# EasyBMS.net
KiCad netlist of a schematic drawn in EAGLE
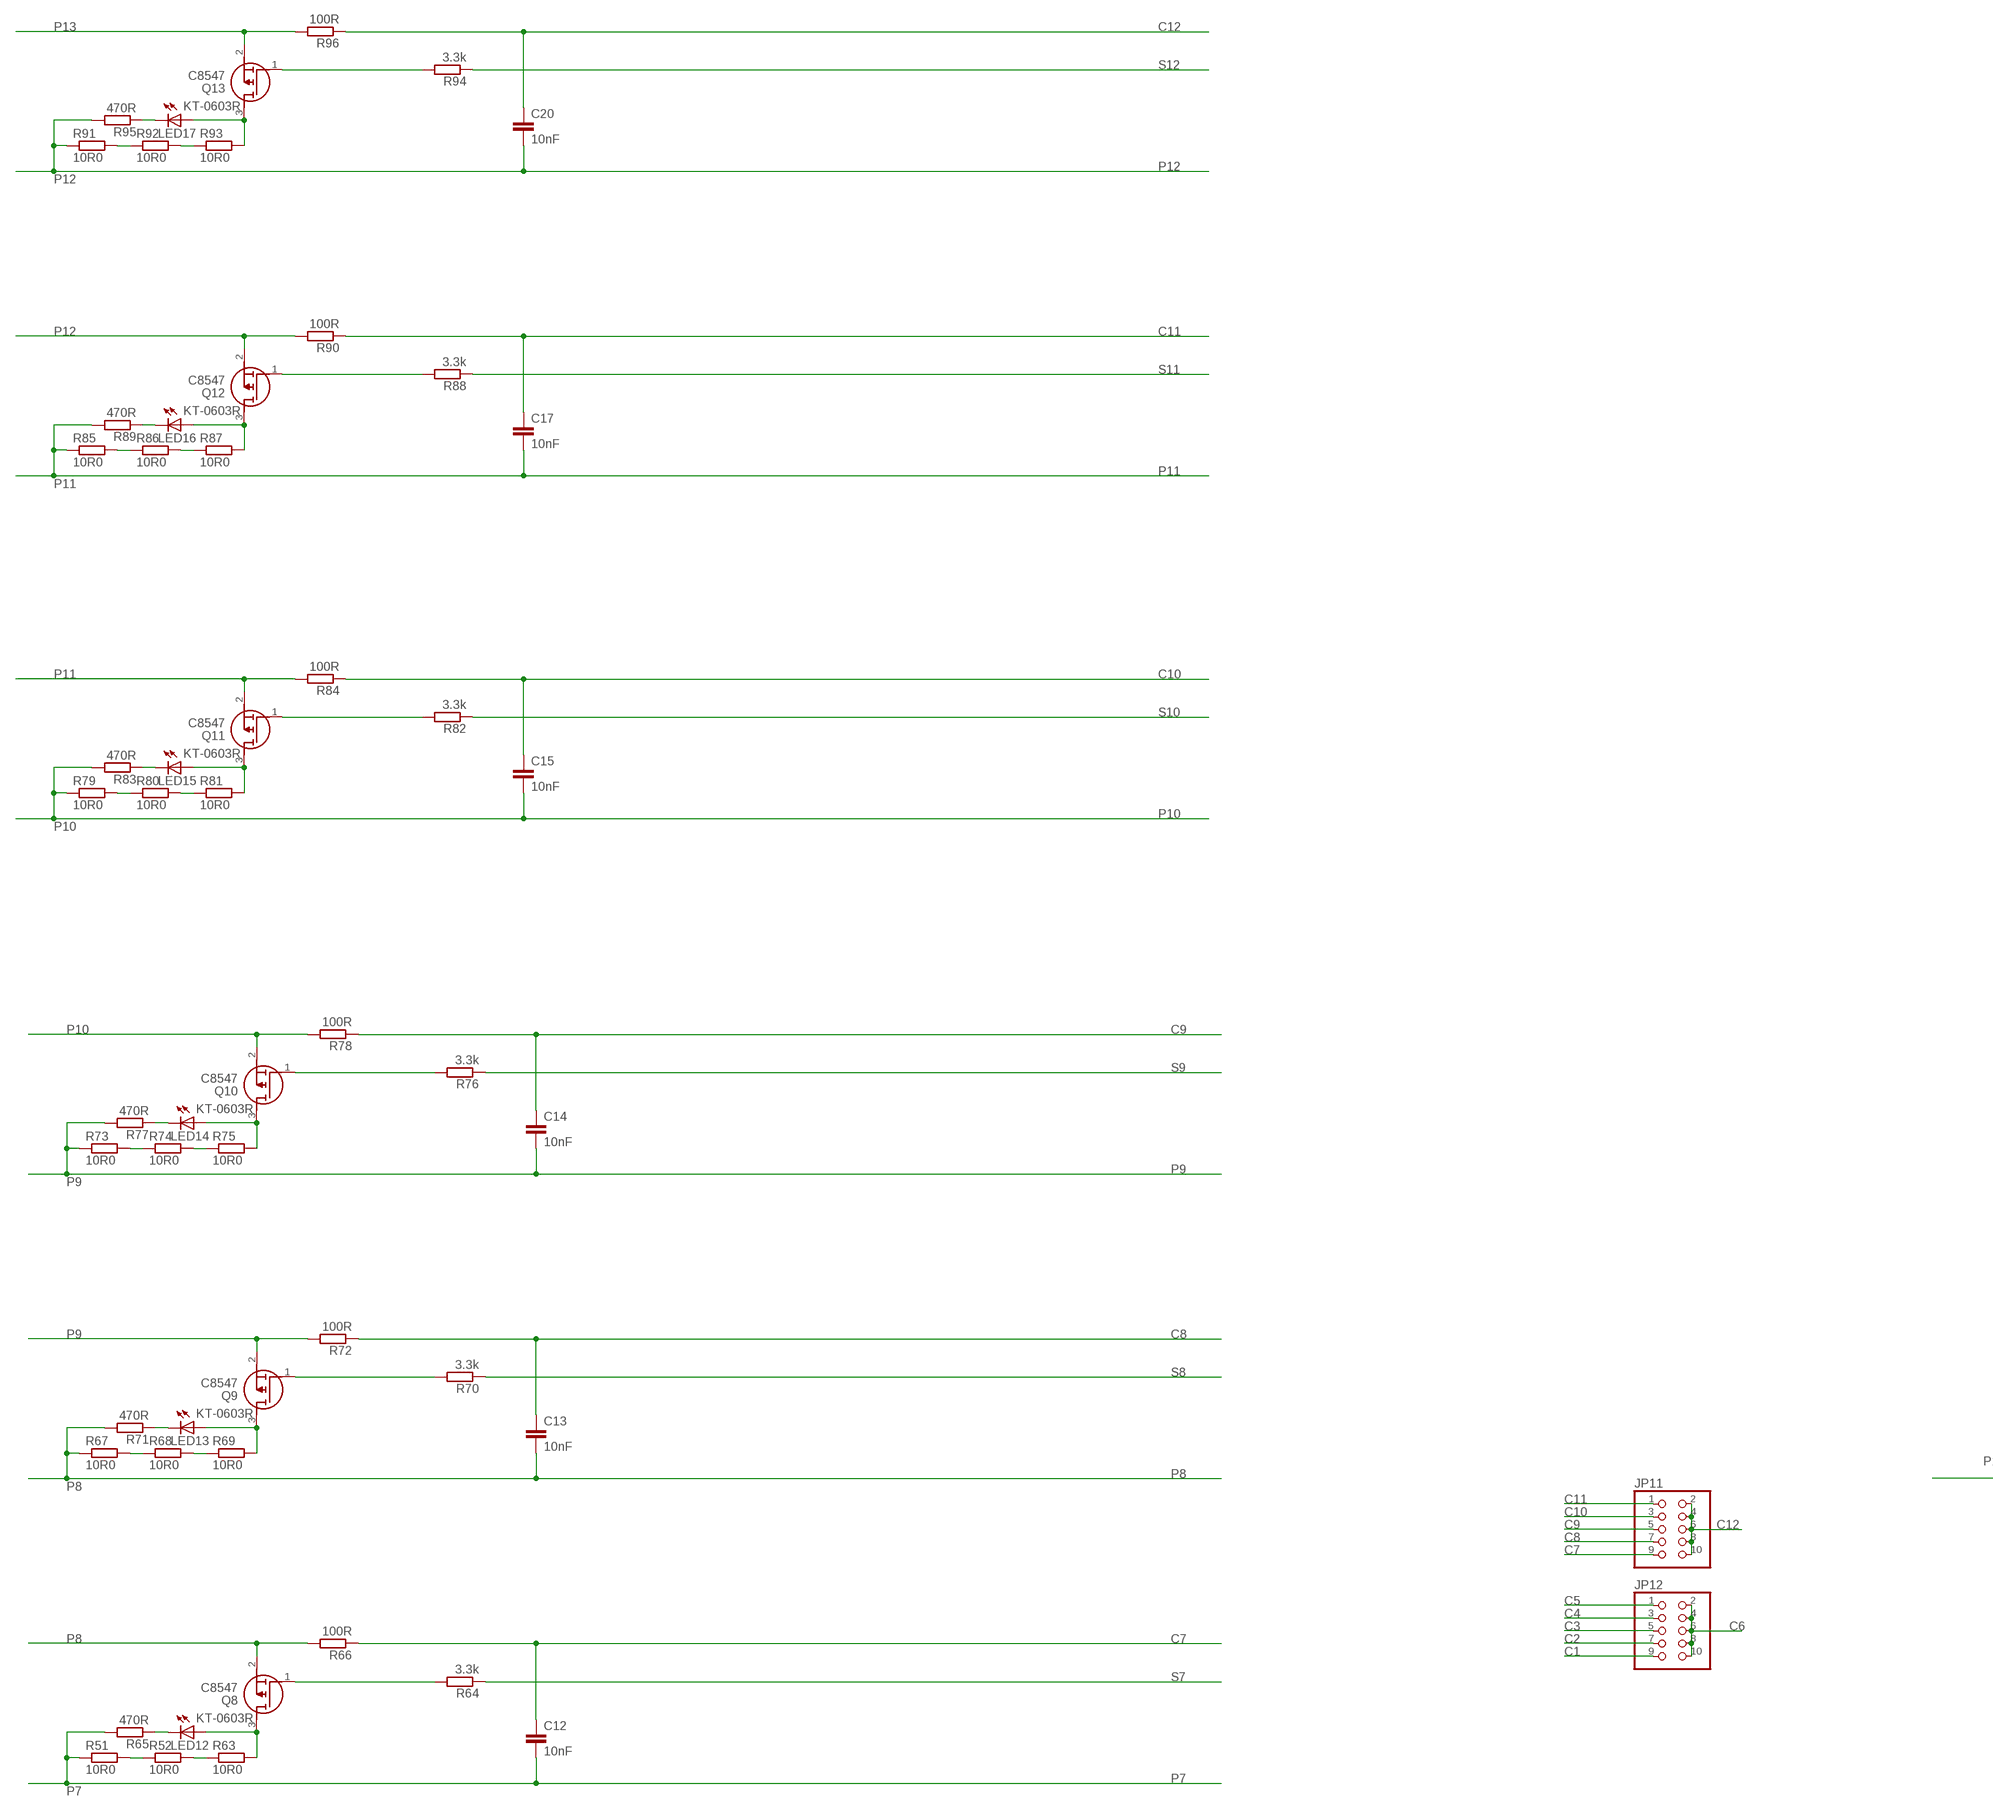
[diagram p0: schematic, sheet 1, part 1 of 3]
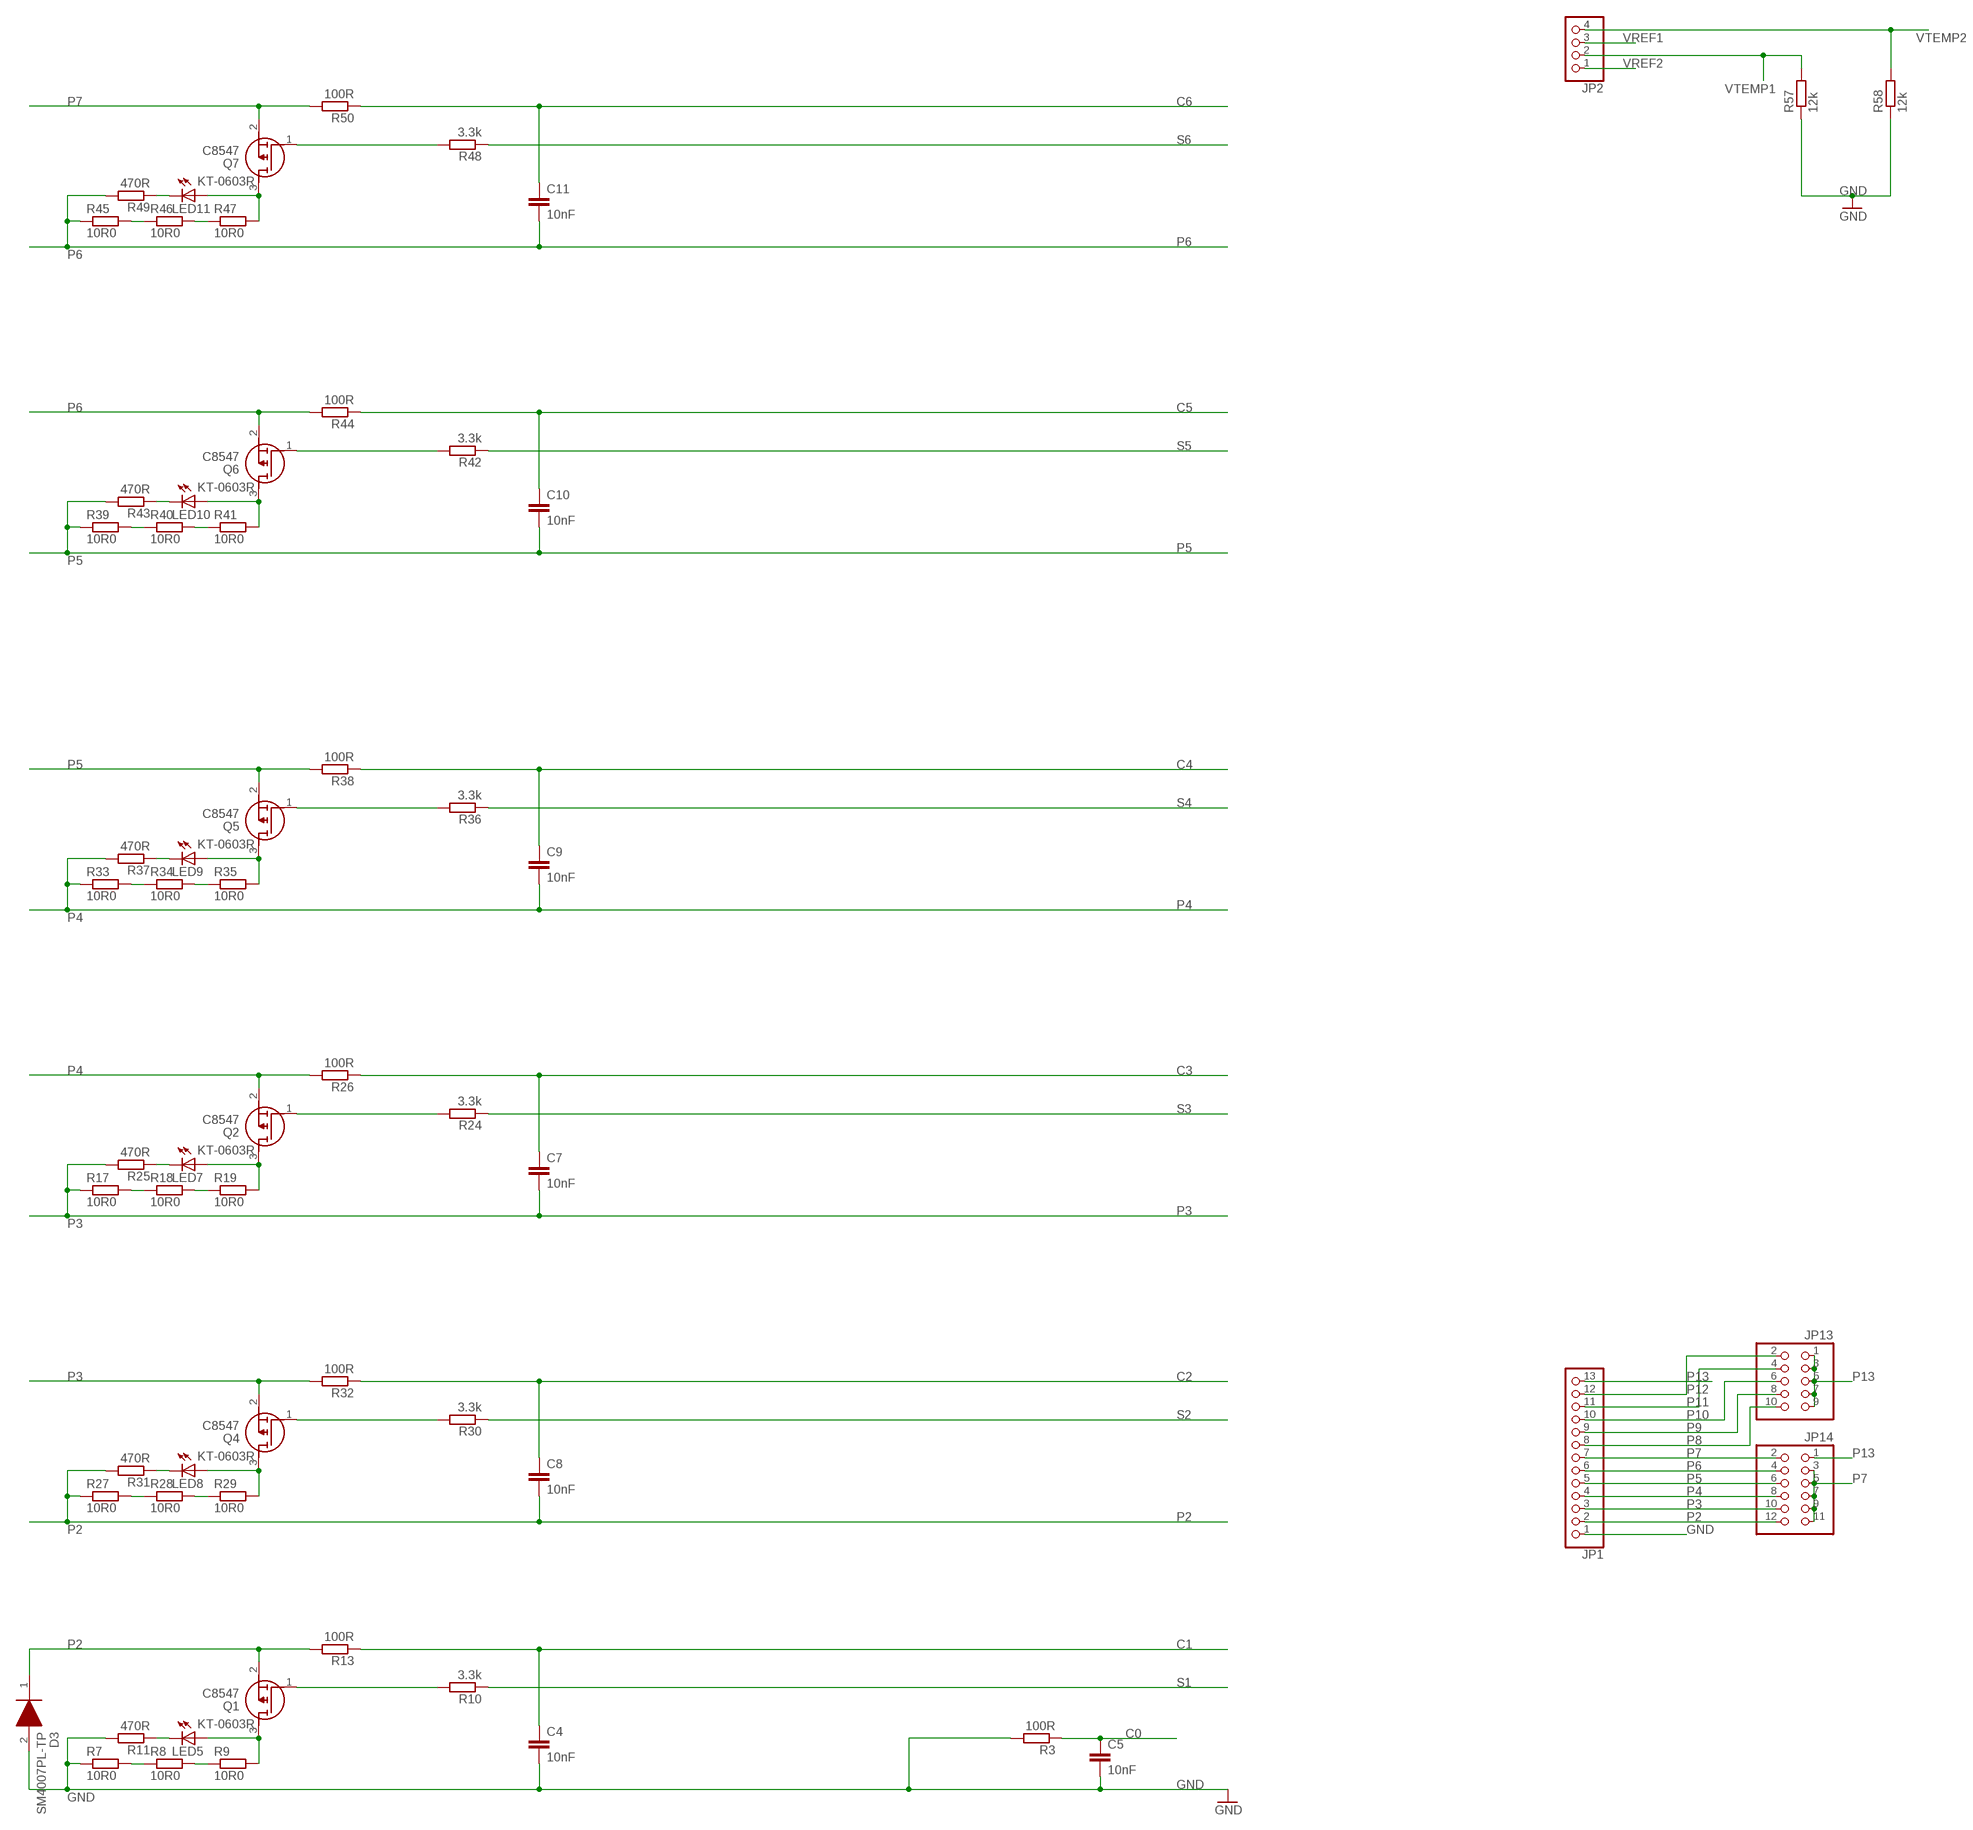
[diagram p1: schematic, sheet 1, part 2 of 3]
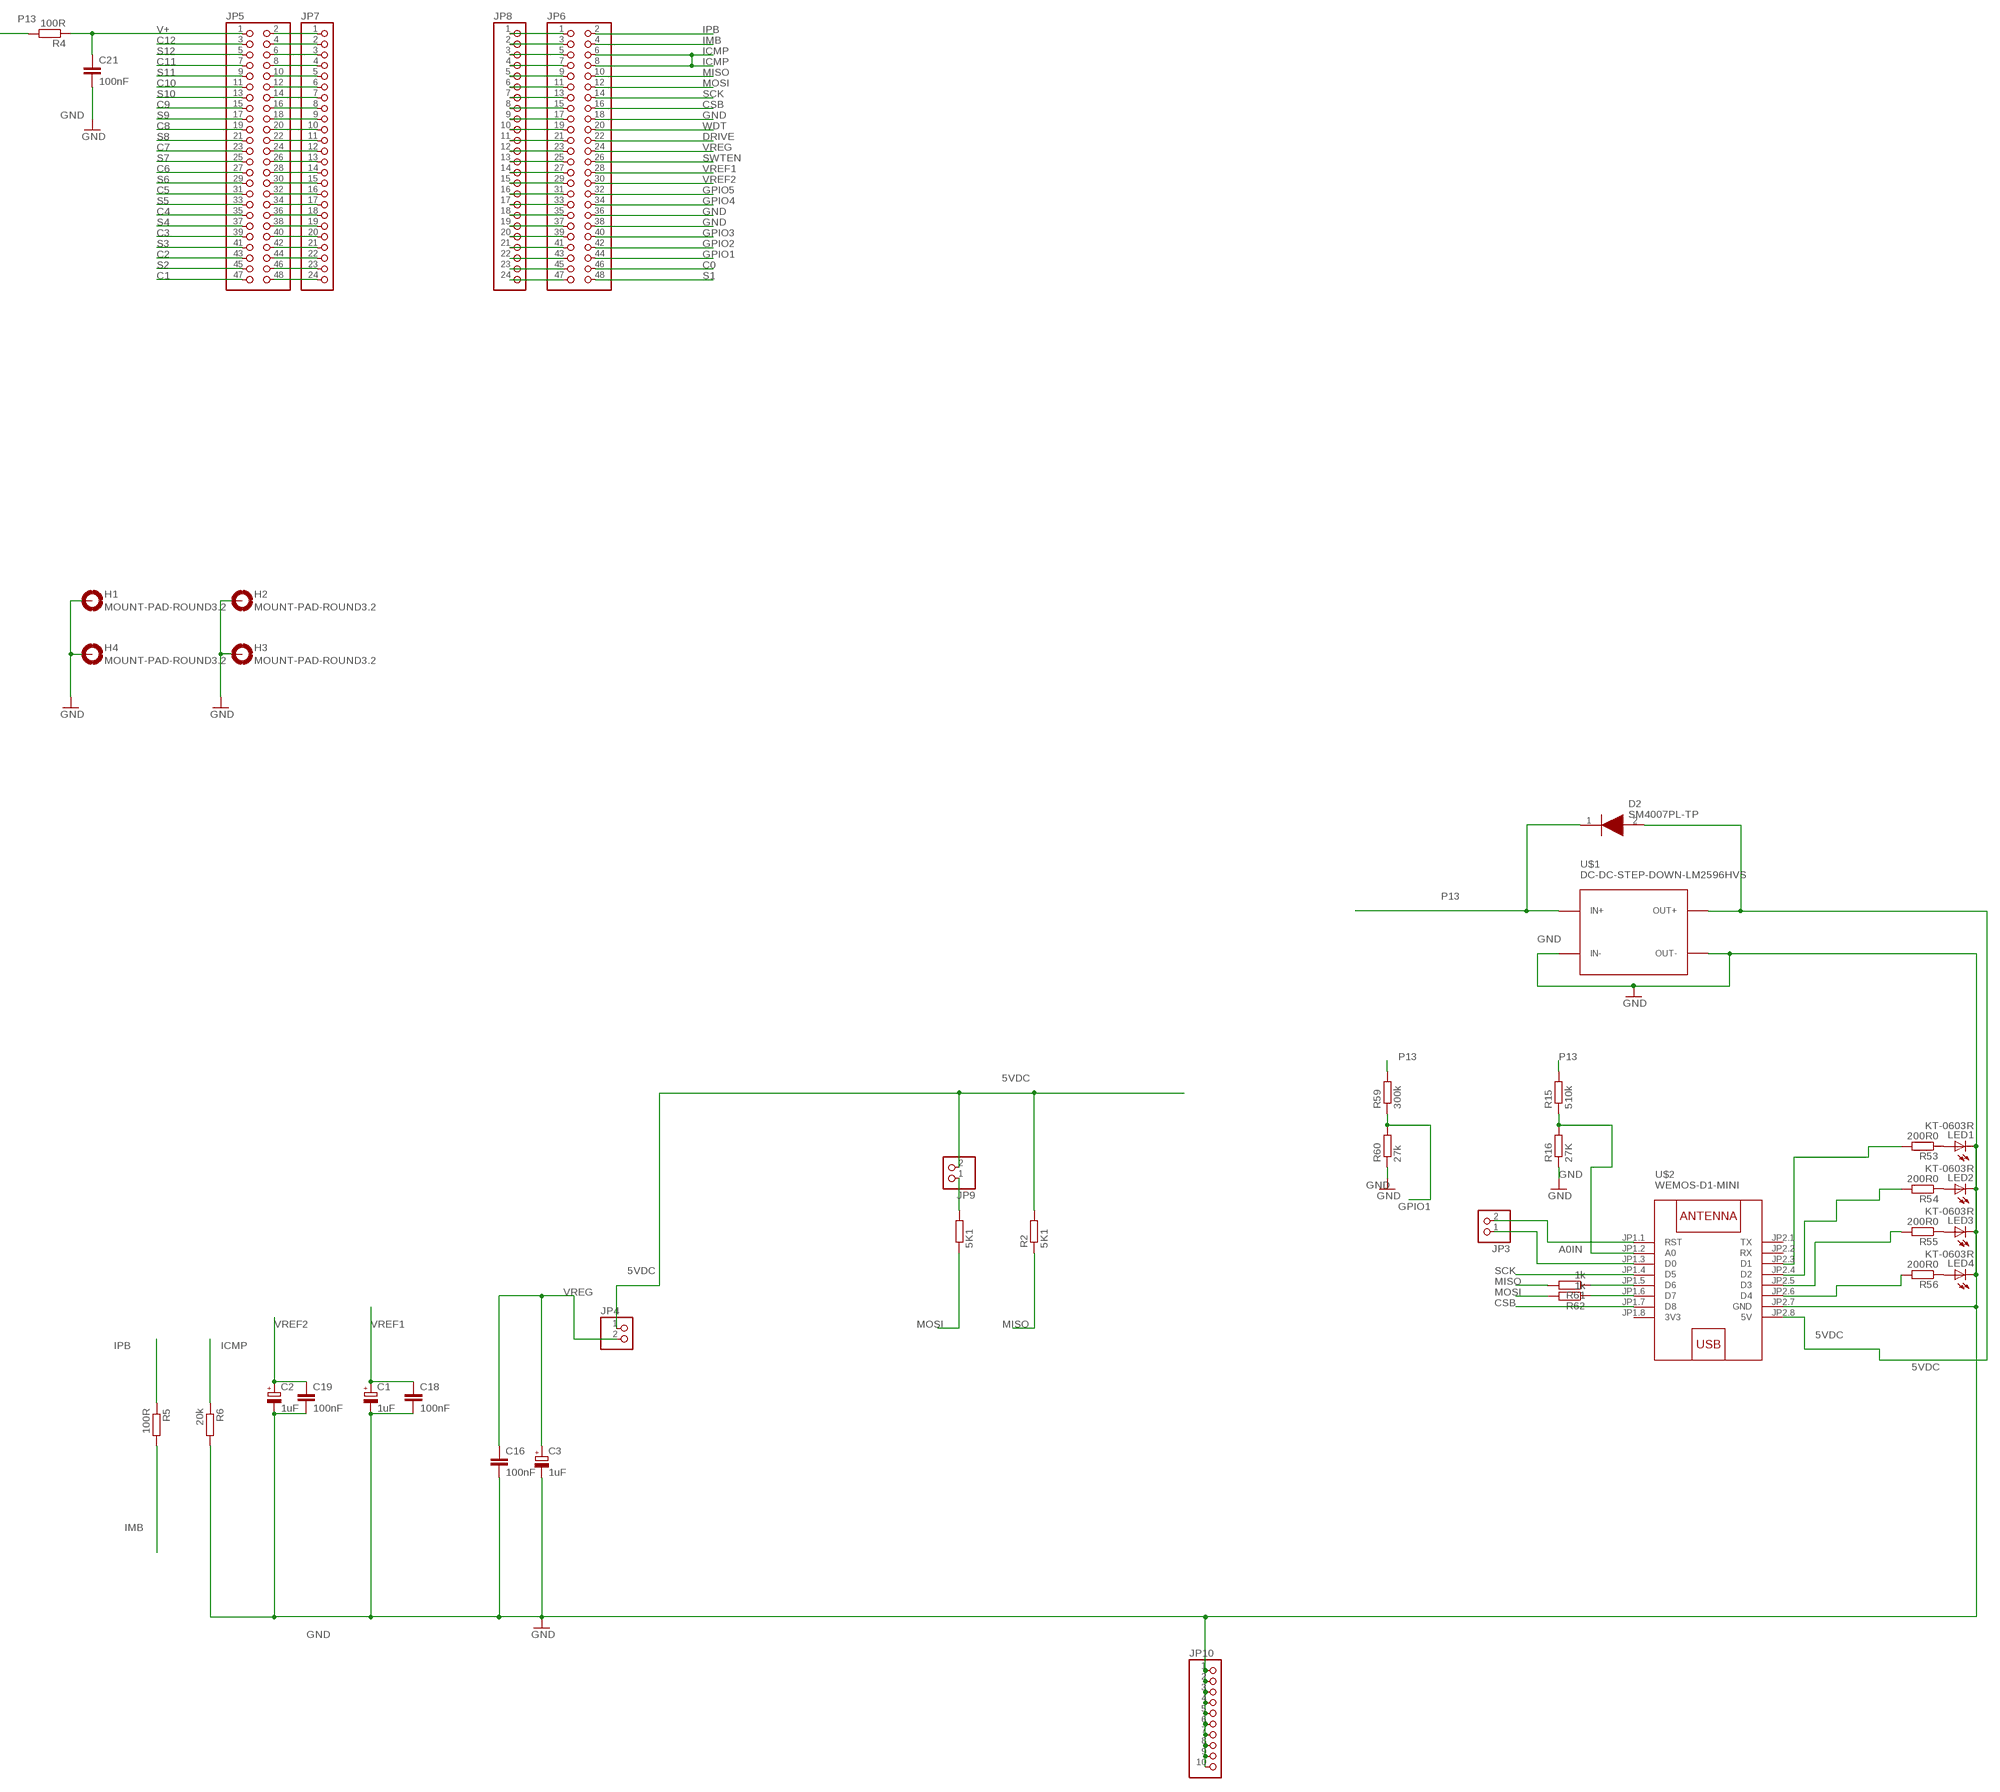
[diagram p2: schematic, sheet 1, part 3 of 3]

(export (version "E")
  (design (tool "Eeschema 10.0.6"))
  (components
    (comp (ref "C1")
      (value "1uF")
      (footprint "eagle-import:E2,5-6")
      (libsource (lib "eagle-import") (part "CPOL-EUE2.5-6"))
    )
    (comp (ref "C2")
      (value "1uF")
      (footprint "eagle-import:E2,5-6")
      (libsource (lib "eagle-import") (part "CPOL-EUE2.5-6"))
    )
    (comp (ref "C3")
      (value "1uF")
      (footprint "eagle-import:E2,5-6")
      (libsource (lib "eagle-import") (part "CPOL-EUE2.5-6"))
    )
    (comp (ref "C4")
      (value "10nF")
      (footprint "eagle-import:C0402")
      (libsource (lib "eagle-import") (part "C-EUC0402"))
    )
    (comp (ref "C5")
      (value "10nF")
      (footprint "eagle-import:C0402")
      (libsource (lib "eagle-import") (part "C-EUC0402"))
    )
    (comp (ref "C7")
      (value "10nF")
      (footprint "eagle-import:C0402")
      (libsource (lib "eagle-import") (part "C-EUC0402"))
    )
    (comp (ref "C8")
      (value "10nF")
      (footprint "eagle-import:C0402")
      (libsource (lib "eagle-import") (part "C-EUC0402"))
    )
    (comp (ref "C9")
      (value "10nF")
      (footprint "eagle-import:C0402")
      (libsource (lib "eagle-import") (part "C-EUC0402"))
    )
    (comp (ref "C10")
      (value "10nF")
      (footprint "eagle-import:C0402")
      (libsource (lib "eagle-import") (part "C-EUC0402"))
    )
    (comp (ref "C11")
      (value "10nF")
      (footprint "eagle-import:C0402")
      (libsource (lib "eagle-import") (part "C-EUC0402"))
    )
    (comp (ref "C12")
      (value "10nF")
      (footprint "eagle-import:C0402")
      (libsource (lib "eagle-import") (part "C-EUC0402"))
    )
    (comp (ref "C13")
      (value "10nF")
      (footprint "eagle-import:C0402")
      (libsource (lib "eagle-import") (part "C-EUC0402"))
    )
    (comp (ref "C14")
      (value "10nF")
      (footprint "eagle-import:C0402")
      (libsource (lib "eagle-import") (part "C-EUC0402"))
    )
    (comp (ref "C15")
      (value "10nF")
      (footprint "eagle-import:C0402")
      (libsource (lib "eagle-import") (part "C-EUC0402"))
    )
    (comp (ref "C16")
      (value "100nF")
      (footprint "eagle-import:C1206")
      (libsource (lib "eagle-import") (part "C-EUC1206"))
    )
    (comp (ref "C17")
      (value "10nF")
      (footprint "eagle-import:C0402")
      (libsource (lib "eagle-import") (part "C-EUC0402"))
    )
    (comp (ref "C18")
      (value "100nF")
      (footprint "eagle-import:C1206")
      (libsource (lib "eagle-import") (part "C-EUC1206"))
    )
    (comp (ref "C19")
      (value "100nF")
      (footprint "eagle-import:C1206")
      (libsource (lib "eagle-import") (part "C-EUC1206"))
    )
    (comp (ref "C20")
      (value "10nF")
      (footprint "eagle-import:C0402")
      (libsource (lib "eagle-import") (part "C-EUC0402"))
    )
    (comp (ref "C21")
      (value "100nF")
      (footprint "eagle-import:C1206")
      (libsource (lib "eagle-import") (part "C-EUC1206"))
    )
    (comp (ref "D2")
      (value "SM4007PL-TP")
      (footprint "eagle-import:SODFL3616X135N")
      (fields (field (name "MOUSER_PART_NUMBER") "833-SM4007PL-TP"))
      (libsource (lib "eagle-import") (part "SM4007PL-TP"))
    )
    (comp (ref "D3")
      (value "SM4007PL-TP")
      (footprint "eagle-import:SODFL3616X135N")
      (fields (field (name "MOUSER_PART_NUMBER") "833-SM4007PL-TP"))
      (libsource (lib "eagle-import") (part "SM4007PL-TP"))
    )
    (comp (ref "H1")
      (value "MOUNT-PAD-ROUND3.2")
      (footprint "eagle-import:3,2-PAD")
      (libsource (lib "eagle-import") (part "MOUNT-PAD-ROUND3.2"))
    )
    (comp (ref "H2")
      (value "MOUNT-PAD-ROUND3.2")
      (footprint "eagle-import:3,2-PAD")
      (libsource (lib "eagle-import") (part "MOUNT-PAD-ROUND3.2"))
    )
    (comp (ref "H3")
      (value "MOUNT-PAD-ROUND3.2")
      (footprint "eagle-import:3,2-PAD")
      (libsource (lib "eagle-import") (part "MOUNT-PAD-ROUND3.2"))
    )
    (comp (ref "H4")
      (value "MOUNT-PAD-ROUND3.2")
      (footprint "eagle-import:3,2-PAD")
      (libsource (lib "eagle-import") (part "MOUNT-PAD-ROUND3.2"))
    )
    (comp (ref "JP1")
      (value "PINHD-1X13/90")
      (footprint "eagle-import:1X13_90")
      (libsource (lib "eagle-import") (part "PINHD-1X13/90"))
    )
    (comp (ref "JP2")
      (value "PINHD-1X4/90")
      (footprint "eagle-import:1X04_90")
      (libsource (lib "eagle-import") (part "PINHD-1X4/90"))
    )
    (comp (ref "JP3")
      (value "PINHD-1X2")
      (footprint "eagle-import:1X02")
      (libsource (lib "eagle-import") (part "PINHD-1X2"))
    )
    (comp (ref "JP4")
      (value "PINHD-1X2")
      (footprint "eagle-import:1X02")
      (libsource (lib "eagle-import") (part "PINHD-1X2"))
    )
    (comp (ref "JP5")
      (value "PINHD-2X24")
      (footprint "eagle-import:2X24")
      (libsource (lib "eagle-import") (part "PINHD-2X24"))
    )
    (comp (ref "JP6")
      (value "PINHD-2X24")
      (footprint "eagle-import:2X24")
      (libsource (lib "eagle-import") (part "PINHD-2X24"))
    )
    (comp (ref "JP7")
      (value "PINHD-1X24")
      (footprint "eagle-import:1X24")
      (libsource (lib "eagle-import") (part "PINHD-1X24"))
    )
    (comp (ref "JP8")
      (value "PINHD-1X24")
      (footprint "eagle-import:1X24")
      (libsource (lib "eagle-import") (part "PINHD-1X24"))
    )
    (comp (ref "JP9")
      (value "PINHD-1X2")
      (footprint "eagle-import:1X02")
      (libsource (lib "eagle-import") (part "PINHD-1X2"))
    )
    (comp (ref "JP10")
      (value "PINHD-1X10")
      (footprint "eagle-import:1X10")
      (libsource (lib "eagle-import") (part "PINHD-1X10"))
    )
    (comp (ref "JP11")
      (value "PINHD-2X5")
      (footprint "eagle-import:2X05")
      (libsource (lib "eagle-import") (part "PINHD-2X5"))
    )
    (comp (ref "JP12")
      (value "PINHD-2X5")
      (footprint "eagle-import:2X05")
      (libsource (lib "eagle-import") (part "PINHD-2X5"))
    )
    (comp (ref "JP13")
      (value "PINHD-2X5")
      (footprint "eagle-import:2X05")
      (libsource (lib "eagle-import") (part "PINHD-2X5"))
    )
    (comp (ref "JP14")
      (value "PINHD-2X6")
      (footprint "eagle-import:2X06")
      (libsource (lib "eagle-import") (part "PINHD-2X6"))
    )
    (comp (ref "LED1")
      (value "KT-0603R")
      (footprint "eagle-import:CHIPLED_0603")
      (libsource (lib "eagle-import") (part "LEDCHIPLED_0603"))
    )
    (comp (ref "LED2")
      (value "KT-0603R")
      (footprint "eagle-import:CHIPLED_0603")
      (libsource (lib "eagle-import") (part "LEDCHIPLED_0603"))
    )
    (comp (ref "LED3")
      (value "KT-0603R")
      (footprint "eagle-import:CHIPLED_0603")
      (libsource (lib "eagle-import") (part "LEDCHIPLED_0603"))
    )
    (comp (ref "LED4")
      (value "KT-0603R")
      (footprint "eagle-import:CHIPLED_0603")
      (libsource (lib "eagle-import") (part "LEDCHIPLED_0603"))
    )
    (comp (ref "LED5")
      (value "KT-0603R")
      (footprint "eagle-import:CHIPLED_0603")
      (libsource (lib "eagle-import") (part "LEDCHIPLED_0603"))
    )
    (comp (ref "LED7")
      (value "KT-0603R")
      (footprint "eagle-import:CHIPLED_0603")
      (libsource (lib "eagle-import") (part "LEDCHIPLED_0603"))
    )
    (comp (ref "LED8")
      (value "KT-0603R")
      (footprint "eagle-import:CHIPLED_0603")
      (libsource (lib "eagle-import") (part "LEDCHIPLED_0603"))
    )
    (comp (ref "LED9")
      (value "KT-0603R")
      (footprint "eagle-import:CHIPLED_0603")
      (libsource (lib "eagle-import") (part "LEDCHIPLED_0603"))
    )
    (comp (ref "LED10")
      (value "KT-0603R")
      (footprint "eagle-import:CHIPLED_0603")
      (libsource (lib "eagle-import") (part "LEDCHIPLED_0603"))
    )
    (comp (ref "LED11")
      (value "KT-0603R")
      (footprint "eagle-import:CHIPLED_0603")
      (libsource (lib "eagle-import") (part "LEDCHIPLED_0603"))
    )
    (comp (ref "LED12")
      (value "KT-0603R")
      (footprint "eagle-import:CHIPLED_0603")
      (libsource (lib "eagle-import") (part "LEDCHIPLED_0603"))
    )
    (comp (ref "LED13")
      (value "KT-0603R")
      (footprint "eagle-import:CHIPLED_0603")
      (libsource (lib "eagle-import") (part "LEDCHIPLED_0603"))
    )
    (comp (ref "LED14")
      (value "KT-0603R")
      (footprint "eagle-import:CHIPLED_0603")
      (libsource (lib "eagle-import") (part "LEDCHIPLED_0603"))
    )
    (comp (ref "LED15")
      (value "KT-0603R")
      (footprint "eagle-import:CHIPLED_0603")
      (libsource (lib "eagle-import") (part "LEDCHIPLED_0603"))
    )
    (comp (ref "LED16")
      (value "KT-0603R")
      (footprint "eagle-import:CHIPLED_0603")
      (libsource (lib "eagle-import") (part "LEDCHIPLED_0603"))
    )
    (comp (ref "LED17")
      (value "KT-0603R")
      (footprint "eagle-import:CHIPLED_0603")
      (libsource (lib "eagle-import") (part "LEDCHIPLED_0603"))
    )
    (comp (ref "Q1")
      (value "C8547")
      (footprint "eagle-import:PG-SOT-23")
      (fields
        (field (name "MANUFACTURER_PART_NUMBER") "BSS308PEH6327XTSA1")
        (field (name "MOUSER_PART_NUMBER") "726-BSS308PEH6327XTS")
      )
      (libsource (lib "eagle-import") (part "BSS308PEH6327XTSA1"))
    )
    (comp (ref "Q2")
      (value "C8547")
      (footprint "eagle-import:PG-SOT-23")
      (fields
        (field (name "MANUFACTURER_PART_NUMBER") "BSS308PEH6327XTSA1")
        (field (name "MOUSER_PART_NUMBER") "726-BSS308PEH6327XTS")
      )
      (libsource (lib "eagle-import") (part "BSS308PEH6327XTSA1"))
    )
    (comp (ref "Q4")
      (value "C8547")
      (footprint "eagle-import:PG-SOT-23")
      (fields
        (field (name "MANUFACTURER_PART_NUMBER") "BSS308PEH6327XTSA1")
        (field (name "MOUSER_PART_NUMBER") "726-BSS308PEH6327XTS")
      )
      (libsource (lib "eagle-import") (part "BSS308PEH6327XTSA1"))
    )
    (comp (ref "Q5")
      (value "C8547")
      (footprint "eagle-import:PG-SOT-23")
      (fields
        (field (name "MANUFACTURER_PART_NUMBER") "BSS308PEH6327XTSA1")
        (field (name "MOUSER_PART_NUMBER") "726-BSS308PEH6327XTS")
      )
      (libsource (lib "eagle-import") (part "BSS308PEH6327XTSA1"))
    )
    (comp (ref "Q6")
      (value "C8547")
      (footprint "eagle-import:PG-SOT-23")
      (fields
        (field (name "MANUFACTURER_PART_NUMBER") "BSS308PEH6327XTSA1")
        (field (name "MOUSER_PART_NUMBER") "726-BSS308PEH6327XTS")
      )
      (libsource (lib "eagle-import") (part "BSS308PEH6327XTSA1"))
    )
    (comp (ref "Q7")
      (value "C8547")
      (footprint "eagle-import:PG-SOT-23")
      (fields
        (field (name "MANUFACTURER_PART_NUMBER") "BSS308PEH6327XTSA1")
        (field (name "MOUSER_PART_NUMBER") "726-BSS308PEH6327XTS")
      )
      (libsource (lib "eagle-import") (part "BSS308PEH6327XTSA1"))
    )
    (comp (ref "Q8")
      (value "C8547")
      (footprint "eagle-import:PG-SOT-23")
      (fields
        (field (name "MANUFACTURER_PART_NUMBER") "BSS308PEH6327XTSA1")
        (field (name "MOUSER_PART_NUMBER") "726-BSS308PEH6327XTS")
      )
      (libsource (lib "eagle-import") (part "BSS308PEH6327XTSA1"))
    )
    (comp (ref "Q9")
      (value "C8547")
      (footprint "eagle-import:PG-SOT-23")
      (fields
        (field (name "MANUFACTURER_PART_NUMBER") "BSS308PEH6327XTSA1")
        (field (name "MOUSER_PART_NUMBER") "726-BSS308PEH6327XTS")
      )
      (libsource (lib "eagle-import") (part "BSS308PEH6327XTSA1"))
    )
    (comp (ref "Q10")
      (value "C8547")
      (footprint "eagle-import:PG-SOT-23")
      (fields
        (field (name "MANUFACTURER_PART_NUMBER") "BSS308PEH6327XTSA1")
        (field (name "MOUSER_PART_NUMBER") "726-BSS308PEH6327XTS")
      )
      (libsource (lib "eagle-import") (part "BSS308PEH6327XTSA1"))
    )
    (comp (ref "Q11")
      (value "C8547")
      (footprint "eagle-import:PG-SOT-23")
      (fields
        (field (name "MANUFACTURER_PART_NUMBER") "BSS308PEH6327XTSA1")
        (field (name "MOUSER_PART_NUMBER") "726-BSS308PEH6327XTS")
      )
      (libsource (lib "eagle-import") (part "BSS308PEH6327XTSA1"))
    )
    (comp (ref "Q12")
      (value "C8547")
      (footprint "eagle-import:PG-SOT-23")
      (fields
        (field (name "MANUFACTURER_PART_NUMBER") "BSS308PEH6327XTSA1")
        (field (name "MOUSER_PART_NUMBER") "726-BSS308PEH6327XTS")
      )
      (libsource (lib "eagle-import") (part "BSS308PEH6327XTSA1"))
    )
    (comp (ref "Q13")
      (value "C8547")
      (footprint "eagle-import:PG-SOT-23")
      (fields
        (field (name "MANUFACTURER_PART_NUMBER") "BSS308PEH6327XTSA1")
        (field (name "MOUSER_PART_NUMBER") "726-BSS308PEH6327XTS")
      )
      (libsource (lib "eagle-import") (part "BSS308PEH6327XTSA1"))
    )
    (comp (ref "R1")
      (value "5K1")
      (footprint "eagle-import:R0603")
      (libsource (lib "eagle-import") (part "R-EU_R0603"))
    )
    (comp (ref "R2")
      (value "5K1")
      (footprint "eagle-import:R0603")
      (libsource (lib "eagle-import") (part "R-EU_R0603"))
    )
    (comp (ref "R3")
      (value "100R")
      (footprint "eagle-import:R0402")
      (libsource (lib "eagle-import") (part "R-EU_R0402"))
    )
    (comp (ref "R4")
      (value "100R")
      (footprint "eagle-import:R0402")
      (libsource (lib "eagle-import") (part "R-EU_R0402"))
    )
    (comp (ref "R5")
      (value "100R")
      (footprint "eagle-import:R0402")
      (libsource (lib "eagle-import") (part "R-EU_R0402"))
    )
    (comp (ref "R6")
      (value "20k")
      (footprint "eagle-import:R0603")
      (libsource (lib "eagle-import") (part "R-EU_R0603"))
    )
    (comp (ref "R7")
      (value "10R0")
      (footprint "eagle-import:R1206")
      (libsource (lib "eagle-import") (part "R-EU_R1206"))
    )
    (comp (ref "R8")
      (value "10R0")
      (footprint "eagle-import:R1206")
      (libsource (lib "eagle-import") (part "R-EU_R1206"))
    )
    (comp (ref "R9")
      (value "10R0")
      (footprint "eagle-import:R1206")
      (libsource (lib "eagle-import") (part "R-EU_R1206"))
    )
    (comp (ref "R10")
      (value "3.3k")
      (footprint "eagle-import:R0402")
      (libsource (lib "eagle-import") (part "R-EU_R0402"))
    )
    (comp (ref "R11")
      (value "470R")
      (footprint "eagle-import:R0402")
      (libsource (lib "eagle-import") (part "R-EU_R0402"))
    )
    (comp (ref "R13")
      (value "100R")
      (footprint "eagle-import:R0402")
      (libsource (lib "eagle-import") (part "R-EU_R0402"))
    )
    (comp (ref "R15")
      (value "510k")
      (footprint "eagle-import:R0603")
      (libsource (lib "eagle-import") (part "R-EU_R0603"))
    )
    (comp (ref "R16")
      (value "27K")
      (footprint "eagle-import:R0603")
      (libsource (lib "eagle-import") (part "R-EU_R0603"))
    )
    (comp (ref "R17")
      (value "10R0")
      (footprint "eagle-import:R1206")
      (libsource (lib "eagle-import") (part "R-EU_R1206"))
    )
    (comp (ref "R18")
      (value "10R0")
      (footprint "eagle-import:R1206")
      (libsource (lib "eagle-import") (part "R-EU_R1206"))
    )
    (comp (ref "R19")
      (value "10R0")
      (footprint "eagle-import:R1206")
      (libsource (lib "eagle-import") (part "R-EU_R1206"))
    )
    (comp (ref "R24")
      (value "3.3k")
      (footprint "eagle-import:R0402")
      (libsource (lib "eagle-import") (part "R-EU_R0402"))
    )
    (comp (ref "R25")
      (value "470R")
      (footprint "eagle-import:R0402")
      (libsource (lib "eagle-import") (part "R-EU_R0402"))
    )
    (comp (ref "R26")
      (value "100R")
      (footprint "eagle-import:R0402")
      (libsource (lib "eagle-import") (part "R-EU_R0402"))
    )
    (comp (ref "R27")
      (value "10R0")
      (footprint "eagle-import:R1206")
      (libsource (lib "eagle-import") (part "R-EU_R1206"))
    )
    (comp (ref "R28")
      (value "10R0")
      (footprint "eagle-import:R1206")
      (libsource (lib "eagle-import") (part "R-EU_R1206"))
    )
    (comp (ref "R29")
      (value "10R0")
      (footprint "eagle-import:R1206")
      (libsource (lib "eagle-import") (part "R-EU_R1206"))
    )
    (comp (ref "R30")
      (value "3.3k")
      (footprint "eagle-import:R0402")
      (libsource (lib "eagle-import") (part "R-EU_R0402"))
    )
    (comp (ref "R31")
      (value "470R")
      (footprint "eagle-import:R0402")
      (libsource (lib "eagle-import") (part "R-EU_R0402"))
    )
    (comp (ref "R32")
      (value "100R")
      (footprint "eagle-import:R0402")
      (libsource (lib "eagle-import") (part "R-EU_R0402"))
    )
    (comp (ref "R33")
      (value "10R0")
      (footprint "eagle-import:R1206")
      (libsource (lib "eagle-import") (part "R-EU_R1206"))
    )
    (comp (ref "R34")
      (value "10R0")
      (footprint "eagle-import:R1206")
      (libsource (lib "eagle-import") (part "R-EU_R1206"))
    )
    (comp (ref "R35")
      (value "10R0")
      (footprint "eagle-import:R1206")
      (libsource (lib "eagle-import") (part "R-EU_R1206"))
    )
    (comp (ref "R36")
      (value "3.3k")
      (footprint "eagle-import:R0402")
      (libsource (lib "eagle-import") (part "R-EU_R0402"))
    )
    (comp (ref "R37")
      (value "470R")
      (footprint "eagle-import:R0402")
      (libsource (lib "eagle-import") (part "R-EU_R0402"))
    )
    (comp (ref "R38")
      (value "100R")
      (footprint "eagle-import:R0402")
      (libsource (lib "eagle-import") (part "R-EU_R0402"))
    )
    (comp (ref "R39")
      (value "10R0")
      (footprint "eagle-import:R1206")
      (libsource (lib "eagle-import") (part "R-EU_R1206"))
    )
    (comp (ref "R40")
      (value "10R0")
      (footprint "eagle-import:R1206")
      (libsource (lib "eagle-import") (part "R-EU_R1206"))
    )
    (comp (ref "R41")
      (value "10R0")
      (footprint "eagle-import:R1206")
      (libsource (lib "eagle-import") (part "R-EU_R1206"))
    )
    (comp (ref "R42")
      (value "3.3k")
      (footprint "eagle-import:R0402")
      (libsource (lib "eagle-import") (part "R-EU_R0402"))
    )
    (comp (ref "R43")
      (value "470R")
      (footprint "eagle-import:R0402")
      (libsource (lib "eagle-import") (part "R-EU_R0402"))
    )
    (comp (ref "R44")
      (value "100R")
      (footprint "eagle-import:R0402")
      (libsource (lib "eagle-import") (part "R-EU_R0402"))
    )
    (comp (ref "R45")
      (value "10R0")
      (footprint "eagle-import:R1206")
      (libsource (lib "eagle-import") (part "R-EU_R1206"))
    )
    (comp (ref "R46")
      (value "10R0")
      (footprint "eagle-import:R1206")
      (libsource (lib "eagle-import") (part "R-EU_R1206"))
    )
    (comp (ref "R47")
      (value "10R0")
      (footprint "eagle-import:R1206")
      (libsource (lib "eagle-import") (part "R-EU_R1206"))
    )
    (comp (ref "R48")
      (value "3.3k")
      (footprint "eagle-import:R0402")
      (libsource (lib "eagle-import") (part "R-EU_R0402"))
    )
    (comp (ref "R49")
      (value "470R")
      (footprint "eagle-import:R0402")
      (libsource (lib "eagle-import") (part "R-EU_R0402"))
    )
    (comp (ref "R50")
      (value "100R")
      (footprint "eagle-import:R0402")
      (libsource (lib "eagle-import") (part "R-EU_R0402"))
    )
    (comp (ref "R51")
      (value "10R0")
      (footprint "eagle-import:R1206")
      (libsource (lib "eagle-import") (part "R-EU_R1206"))
    )
    (comp (ref "R52")
      (value "10R0")
      (footprint "eagle-import:R1206")
      (libsource (lib "eagle-import") (part "R-EU_R1206"))
    )
    (comp (ref "R53")
      (value "200R0")
      (footprint "eagle-import:R0603")
      (libsource (lib "eagle-import") (part "R-EU_R0603"))
    )
    (comp (ref "R54")
      (value "200R0")
      (footprint "eagle-import:R0603")
      (libsource (lib "eagle-import") (part "R-EU_R0603"))
    )
    (comp (ref "R55")
      (value "200R0")
      (footprint "eagle-import:R0603")
      (libsource (lib "eagle-import") (part "R-EU_R0603"))
    )
    (comp (ref "R56")
      (value "200R0")
      (footprint "eagle-import:R0603")
      (libsource (lib "eagle-import") (part "R-EU_R0603"))
    )
    (comp (ref "R57")
      (value "12k")
      (footprint "eagle-import:R0603")
      (libsource (lib "eagle-import") (part "R-EU_R0603"))
    )
    (comp (ref "R58")
      (value "12k")
      (footprint "eagle-import:R0603")
      (libsource (lib "eagle-import") (part "R-EU_R0603"))
    )
    (comp (ref "R59")
      (value "300k")
      (footprint "eagle-import:R0603")
      (libsource (lib "eagle-import") (part "R-EU_R0603"))
    )
    (comp (ref "R60")
      (value "27k")
      (footprint "eagle-import:R0603")
      (libsource (lib "eagle-import") (part "R-EU_R0603"))
    )
    (comp (ref "R61")
      (value "1k")
      (footprint "eagle-import:R0603")
      (libsource (lib "eagle-import") (part "R-EU_R0603"))
    )
    (comp (ref "R62")
      (value "1k")
      (footprint "eagle-import:R0603")
      (libsource (lib "eagle-import") (part "R-EU_R0603"))
    )
    (comp (ref "R63")
      (value "10R0")
      (footprint "eagle-import:R1206")
      (libsource (lib "eagle-import") (part "R-EU_R1206"))
    )
    (comp (ref "R64")
      (value "3.3k")
      (footprint "eagle-import:R0402")
      (libsource (lib "eagle-import") (part "R-EU_R0402"))
    )
    (comp (ref "R65")
      (value "470R")
      (footprint "eagle-import:R0402")
      (libsource (lib "eagle-import") (part "R-EU_R0402"))
    )
    (comp (ref "R66")
      (value "100R")
      (footprint "eagle-import:R0402")
      (libsource (lib "eagle-import") (part "R-EU_R0402"))
    )
    (comp (ref "R67")
      (value "10R0")
      (footprint "eagle-import:R1206")
      (libsource (lib "eagle-import") (part "R-EU_R1206"))
    )
    (comp (ref "R68")
      (value "10R0")
      (footprint "eagle-import:R1206")
      (libsource (lib "eagle-import") (part "R-EU_R1206"))
    )
    (comp (ref "R69")
      (value "10R0")
      (footprint "eagle-import:R1206")
      (libsource (lib "eagle-import") (part "R-EU_R1206"))
    )
    (comp (ref "R70")
      (value "3.3k")
      (footprint "eagle-import:R0402")
      (libsource (lib "eagle-import") (part "R-EU_R0402"))
    )
    (comp (ref "R71")
      (value "470R")
      (footprint "eagle-import:R0402")
      (libsource (lib "eagle-import") (part "R-EU_R0402"))
    )
    (comp (ref "R72")
      (value "100R")
      (footprint "eagle-import:R0402")
      (libsource (lib "eagle-import") (part "R-EU_R0402"))
    )
    (comp (ref "R73")
      (value "10R0")
      (footprint "eagle-import:R1206")
      (libsource (lib "eagle-import") (part "R-EU_R1206"))
    )
    (comp (ref "R74")
      (value "10R0")
      (footprint "eagle-import:R1206")
      (libsource (lib "eagle-import") (part "R-EU_R1206"))
    )
    (comp (ref "R75")
      (value "10R0")
      (footprint "eagle-import:R1206")
      (libsource (lib "eagle-import") (part "R-EU_R1206"))
    )
    (comp (ref "R76")
      (value "3.3k")
      (footprint "eagle-import:R0402")
      (libsource (lib "eagle-import") (part "R-EU_R0402"))
    )
    (comp (ref "R77")
      (value "470R")
      (footprint "eagle-import:R0402")
      (libsource (lib "eagle-import") (part "R-EU_R0402"))
    )
    (comp (ref "R78")
      (value "100R")
      (footprint "eagle-import:R0402")
      (libsource (lib "eagle-import") (part "R-EU_R0402"))
    )
    (comp (ref "R79")
      (value "10R0")
      (footprint "eagle-import:R1206")
      (libsource (lib "eagle-import") (part "R-EU_R1206"))
    )
    (comp (ref "R80")
      (value "10R0")
      (footprint "eagle-import:R1206")
      (libsource (lib "eagle-import") (part "R-EU_R1206"))
    )
    (comp (ref "R81")
      (value "10R0")
      (footprint "eagle-import:R1206")
      (libsource (lib "eagle-import") (part "R-EU_R1206"))
    )
    (comp (ref "R82")
      (value "3.3k")
      (footprint "eagle-import:R0402")
      (libsource (lib "eagle-import") (part "R-EU_R0402"))
    )
    (comp (ref "R83")
      (value "470R")
      (footprint "eagle-import:R0402")
      (libsource (lib "eagle-import") (part "R-EU_R0402"))
    )
    (comp (ref "R84")
      (value "100R")
      (footprint "eagle-import:R0402")
      (libsource (lib "eagle-import") (part "R-EU_R0402"))
    )
    (comp (ref "R85")
      (value "10R0")
      (footprint "eagle-import:R1206")
      (libsource (lib "eagle-import") (part "R-EU_R1206"))
    )
    (comp (ref "R86")
      (value "10R0")
      (footprint "eagle-import:R1206")
      (libsource (lib "eagle-import") (part "R-EU_R1206"))
    )
    (comp (ref "R87")
      (value "10R0")
      (footprint "eagle-import:R1206")
      (libsource (lib "eagle-import") (part "R-EU_R1206"))
    )
    (comp (ref "R88")
      (value "3.3k")
      (footprint "eagle-import:R0402")
      (libsource (lib "eagle-import") (part "R-EU_R0402"))
    )
    (comp (ref "R89")
      (value "470R")
      (footprint "eagle-import:R0402")
      (libsource (lib "eagle-import") (part "R-EU_R0402"))
    )
    (comp (ref "R90")
      (value "100R")
      (footprint "eagle-import:R0402")
      (libsource (lib "eagle-import") (part "R-EU_R0402"))
    )
    (comp (ref "R91")
      (value "10R0")
      (footprint "eagle-import:R1206")
      (libsource (lib "eagle-import") (part "R-EU_R1206"))
    )
    (comp (ref "R92")
      (value "10R0")
      (footprint "eagle-import:R1206")
      (libsource (lib "eagle-import") (part "R-EU_R1206"))
    )
    (comp (ref "R93")
      (value "10R0")
      (footprint "eagle-import:R1206")
      (libsource (lib "eagle-import") (part "R-EU_R1206"))
    )
    (comp (ref "R94")
      (value "3.3k")
      (footprint "eagle-import:R0402")
      (libsource (lib "eagle-import") (part "R-EU_R0402"))
    )
    (comp (ref "R95")
      (value "470R")
      (footprint "eagle-import:R0402")
      (libsource (lib "eagle-import") (part "R-EU_R0402"))
    )
    (comp (ref "R96")
      (value "100R")
      (footprint "eagle-import:R0402")
      (libsource (lib "eagle-import") (part "R-EU_R0402"))
    )
    (comp (ref "U$1")
      (value "DC-DC-STEP-DOWN-LM2596HVS")
      (footprint "eagle-import:DC-DC-STEP-DOWN-LM2596HVS")
      (libsource (lib "eagle-import") (part "DC-DC-STEP-DOWN-LM2596HVS"))
    )
    (comp (ref "U$2")
      (value "WEMOS-D1-MINI")
      (footprint "eagle-import:WEMOS-D1-MINI")
      (libsource (lib "eagle-import") (part "WEMOS-D1-MINI"))
    )
  )
  (nets
    (net (code "1") (name "/3V3") (class "Default")
      (node (ref "U$2") (pin "JP1.8") (pinfunction "3V3_JP1.8") (pintype "power_in"))
    )
    (net (code "2") (name "/5VDC") (class "Default")
      (node (ref "D2") (pin "2") (pinfunction "A_2") (pintype "bidirectional"))
      (node (ref "JP4") (pin "1") (pinfunction "1_1") (pintype "passive"))
      (node (ref "JP9") (pin "2") (pinfunction "2_2") (pintype "passive"))
      (node (ref "R2") (pin "2") (pinfunction "2_2") (pintype "passive"))
      (node (ref "U$1") (pin "OUT+") (pinfunction "OUT+_OUT+") (pintype "bidirectional"))
      (node (ref "U$2") (pin "JP2.8") (pinfunction "5V_JP2.8") (pintype "power_in"))
    )
    (net (code "3") (name "/A0IN") (class "Default")
      (node (ref "R15") (pin "1") (pinfunction "1_1") (pintype "passive"))
      (node (ref "R16") (pin "2") (pinfunction "2_2") (pintype "passive"))
      (node (ref "U$2") (pin "JP1.2") (pinfunction "A0_JP1.2") (pintype "bidirectional"))
    )
    (net (code "4") (name "/C0") (class "Default")
      (node (ref "C5") (pin "1") (pinfunction "1_1") (pintype "passive"))
      (node (ref "JP6") (pin "46") (pinfunction "46_46") (pintype "passive"))
      (node (ref "R3") (pin "1") (pinfunction "1_1") (pintype "passive"))
    )
    (net (code "5") (name "/C1") (class "Default")
      (node (ref "C4") (pin "1") (pinfunction "1_1") (pintype "passive"))
      (node (ref "JP12") (pin "9") (pinfunction "9_9") (pintype "passive"))
      (node (ref "JP5") (pin "47") (pinfunction "47_47") (pintype "passive"))
      (node (ref "R13") (pin "1") (pinfunction "1_1") (pintype "passive"))
    )
    (net (code "6") (name "/C2") (class "Default")
      (node (ref "C8") (pin "1") (pinfunction "1_1") (pintype "passive"))
      (node (ref "JP12") (pin "7") (pinfunction "7_7") (pintype "passive"))
      (node (ref "JP5") (pin "43") (pinfunction "43_43") (pintype "passive"))
      (node (ref "R32") (pin "1") (pinfunction "1_1") (pintype "passive"))
    )
    (net (code "7") (name "/C3") (class "Default")
      (node (ref "C7") (pin "1") (pinfunction "1_1") (pintype "passive"))
      (node (ref "JP12") (pin "5") (pinfunction "5_5") (pintype "passive"))
      (node (ref "JP5") (pin "39") (pinfunction "39_39") (pintype "passive"))
      (node (ref "R26") (pin "1") (pinfunction "1_1") (pintype "passive"))
    )
    (net (code "8") (name "/C4") (class "Default")
      (node (ref "C9") (pin "1") (pinfunction "1_1") (pintype "passive"))
      (node (ref "JP12") (pin "3") (pinfunction "3_3") (pintype "passive"))
      (node (ref "JP5") (pin "35") (pinfunction "35_35") (pintype "passive"))
      (node (ref "R38") (pin "1") (pinfunction "1_1") (pintype "passive"))
    )
    (net (code "9") (name "/C5") (class "Default")
      (node (ref "C10") (pin "1") (pinfunction "1_1") (pintype "passive"))
      (node (ref "JP12") (pin "1") (pinfunction "1_1") (pintype "passive"))
      (node (ref "JP5") (pin "31") (pinfunction "31_31") (pintype "passive"))
      (node (ref "R44") (pin "1") (pinfunction "1_1") (pintype "passive"))
    )
    (net (code "10") (name "/C6") (class "Default")
      (node (ref "C11") (pin "1") (pinfunction "1_1") (pintype "passive"))
      (node (ref "JP12") (pin "10") (pinfunction "10_10") (pintype "passive"))
      (node (ref "JP12") (pin "2") (pinfunction "2_2") (pintype "passive"))
      (node (ref "JP12") (pin "4") (pinfunction "4_4") (pintype "passive"))
      (node (ref "JP12") (pin "6") (pinfunction "6_6") (pintype "passive"))
      (node (ref "JP12") (pin "8") (pinfunction "8_8") (pintype "passive"))
      (node (ref "JP5") (pin "27") (pinfunction "27_27") (pintype "passive"))
      (node (ref "R50") (pin "1") (pinfunction "1_1") (pintype "passive"))
    )
    (net (code "11") (name "/C7") (class "Default")
      (node (ref "C12") (pin "1") (pinfunction "1_1") (pintype "passive"))
      (node (ref "JP11") (pin "9") (pinfunction "9_9") (pintype "passive"))
      (node (ref "JP5") (pin "23") (pinfunction "23_23") (pintype "passive"))
      (node (ref "R66") (pin "1") (pinfunction "1_1") (pintype "passive"))
    )
    (net (code "12") (name "/C8") (class "Default")
      (node (ref "C13") (pin "1") (pinfunction "1_1") (pintype "passive"))
      (node (ref "JP11") (pin "7") (pinfunction "7_7") (pintype "passive"))
      (node (ref "JP5") (pin "19") (pinfunction "19_19") (pintype "passive"))
      (node (ref "R72") (pin "1") (pinfunction "1_1") (pintype "passive"))
    )
    (net (code "13") (name "/C9") (class "Default")
      (node (ref "C14") (pin "1") (pinfunction "1_1") (pintype "passive"))
      (node (ref "JP11") (pin "5") (pinfunction "5_5") (pintype "passive"))
      (node (ref "JP5") (pin "15") (pinfunction "15_15") (pintype "passive"))
      (node (ref "R78") (pin "1") (pinfunction "1_1") (pintype "passive"))
    )
    (net (code "14") (name "/C10") (class "Default")
      (node (ref "C15") (pin "1") (pinfunction "1_1") (pintype "passive"))
      (node (ref "JP11") (pin "3") (pinfunction "3_3") (pintype "passive"))
      (node (ref "JP5") (pin "11") (pinfunction "11_11") (pintype "passive"))
      (node (ref "R84") (pin "1") (pinfunction "1_1") (pintype "passive"))
    )
    (net (code "15") (name "/C11") (class "Default")
      (node (ref "C17") (pin "1") (pinfunction "1_1") (pintype "passive"))
      (node (ref "JP11") (pin "1") (pinfunction "1_1") (pintype "passive"))
      (node (ref "JP5") (pin "7") (pinfunction "7_7") (pintype "passive"))
      (node (ref "R90") (pin "1") (pinfunction "1_1") (pintype "passive"))
    )
    (net (code "16") (name "/C12") (class "Default")
      (node (ref "C20") (pin "1") (pinfunction "1_1") (pintype "passive"))
      (node (ref "JP11") (pin "10") (pinfunction "10_10") (pintype "passive"))
      (node (ref "JP11") (pin "2") (pinfunction "2_2") (pintype "passive"))
      (node (ref "JP11") (pin "4") (pinfunction "4_4") (pintype "passive"))
      (node (ref "JP11") (pin "6") (pinfunction "6_6") (pintype "passive"))
      (node (ref "JP11") (pin "8") (pinfunction "8_8") (pintype "passive"))
      (node (ref "JP5") (pin "3") (pinfunction "3_3") (pintype "passive"))
      (node (ref "R96") (pin "1") (pinfunction "1_1") (pintype "passive"))
    )
    (net (code "17") (name "/CSB") (class "Default")
      (node (ref "JP6") (pin "16") (pinfunction "16_16") (pintype "passive"))
      (node (ref "U$2") (pin "JP1.7") (pinfunction "D8_JP1.7") (pintype "bidirectional"))
    )
    (net (code "18") (name "/DRIVE") (class "Default")
      (node (ref "JP6") (pin "22") (pinfunction "22_22") (pintype "passive"))
    )
    (net (code "19") (name "/GPIO1") (class "Default")
      (node (ref "JP6") (pin "44") (pinfunction "44_44") (pintype "passive"))
      (node (ref "R59") (pin "1") (pinfunction "1_1") (pintype "passive"))
      (node (ref "R60") (pin "2") (pinfunction "2_2") (pintype "passive"))
    )
    (net (code "20") (name "/GPIO2") (class "Default")
      (node (ref "JP6") (pin "42") (pinfunction "42_42") (pintype "passive"))
    )
    (net (code "21") (name "/GPIO3") (class "Default")
      (node (ref "JP6") (pin "40") (pinfunction "40_40") (pintype "passive"))
    )
    (net (code "22") (name "/GPIO4") (class "Default")
      (node (ref "JP6") (pin "34") (pinfunction "34_34") (pintype "passive"))
    )
    (net (code "23") (name "/GPIO5") (class "Default")
      (node (ref "JP6") (pin "32") (pinfunction "32_32") (pintype "passive"))
    )
    (net (code "24") (name "/ICMP") (class "Default")
      (node (ref "JP6") (pin "6") (pinfunction "6_6") (pintype "passive"))
      (node (ref "JP6") (pin "8") (pinfunction "8_8") (pintype "passive"))
      (node (ref "R6") (pin "1") (pinfunction "1_1") (pintype "passive"))
    )
    (net (code "25") (name "/IMB") (class "Default")
      (node (ref "JP6") (pin "4") (pinfunction "4_4") (pintype "passive"))
      (node (ref "R5") (pin "2") (pinfunction "2_2") (pintype "passive"))
    )
    (net (code "26") (name "/IPB") (class "Default")
      (node (ref "JP6") (pin "2") (pinfunction "2_2") (pintype "passive"))
      (node (ref "R5") (pin "1") (pinfunction "1_1") (pintype "passive"))
    )
    (net (code "27") (name "/MISO") (class "Default")
      (node (ref "JP6") (pin "10") (pinfunction "10_10") (pintype "passive"))
      (node (ref "R2") (pin "1") (pinfunction "1_1") (pintype "passive"))
      (node (ref "R61") (pin "2") (pinfunction "2_2") (pintype "passive"))
    )
    (net (code "28") (name "/MOSI") (class "Default")
      (node (ref "JP6") (pin "12") (pinfunction "12_12") (pintype "passive"))
      (node (ref "R1") (pin "1") (pinfunction "1_1") (pintype "passive"))
      (node (ref "R62") (pin "2") (pinfunction "2_2") (pintype "passive"))
    )
    (net (code "29") (name "/P2") (class "Default")
      (node (ref "C8") (pin "2") (pinfunction "2_2") (pintype "passive"))
      (node (ref "D3") (pin "1") (pinfunction "K_1") (pintype "bidirectional"))
      (node (ref "JP1") (pin "2") (pinfunction "2_2") (pintype "passive"))
      (node (ref "JP14") (pin "12") (pinfunction "12_12") (pintype "passive"))
      (node (ref "Q1") (pin "2") (pinfunction "S_2") (pintype "bidirectional"))
      (node (ref "R13") (pin "2") (pinfunction "2_2") (pintype "passive"))
      (node (ref "R27") (pin "1") (pinfunction "1_1") (pintype "passive"))
      (node (ref "R31") (pin "2") (pinfunction "2_2") (pintype "passive"))
    )
    (net (code "30") (name "/P3") (class "Default")
      (node (ref "C7") (pin "2") (pinfunction "2_2") (pintype "passive"))
      (node (ref "JP1") (pin "3") (pinfunction "3_3") (pintype "passive"))
      (node (ref "JP14") (pin "10") (pinfunction "10_10") (pintype "passive"))
      (node (ref "Q4") (pin "2") (pinfunction "S_2") (pintype "bidirectional"))
      (node (ref "R17") (pin "1") (pinfunction "1_1") (pintype "passive"))
      (node (ref "R25") (pin "2") (pinfunction "2_2") (pintype "passive"))
      (node (ref "R32") (pin "2") (pinfunction "2_2") (pintype "passive"))
    )
    (net (code "31") (name "/P4") (class "Default")
      (node (ref "C9") (pin "2") (pinfunction "2_2") (pintype "passive"))
      (node (ref "JP1") (pin "4") (pinfunction "4_4") (pintype "passive"))
      (node (ref "JP14") (pin "8") (pinfunction "8_8") (pintype "passive"))
      (node (ref "Q2") (pin "2") (pinfunction "S_2") (pintype "bidirectional"))
      (node (ref "R26") (pin "2") (pinfunction "2_2") (pintype "passive"))
      (node (ref "R33") (pin "1") (pinfunction "1_1") (pintype "passive"))
      (node (ref "R37") (pin "2") (pinfunction "2_2") (pintype "passive"))
    )
    (net (code "32") (name "/P5") (class "Default")
      (node (ref "C10") (pin "2") (pinfunction "2_2") (pintype "passive"))
      (node (ref "JP1") (pin "5") (pinfunction "5_5") (pintype "passive"))
      (node (ref "JP14") (pin "6") (pinfunction "6_6") (pintype "passive"))
      (node (ref "Q5") (pin "2") (pinfunction "S_2") (pintype "bidirectional"))
      (node (ref "R38") (pin "2") (pinfunction "2_2") (pintype "passive"))
      (node (ref "R39") (pin "1") (pinfunction "1_1") (pintype "passive"))
      (node (ref "R43") (pin "2") (pinfunction "2_2") (pintype "passive"))
    )
    (net (code "33") (name "/P6") (class "Default")
      (node (ref "C11") (pin "2") (pinfunction "2_2") (pintype "passive"))
      (node (ref "JP1") (pin "6") (pinfunction "6_6") (pintype "passive"))
      (node (ref "JP14") (pin "4") (pinfunction "4_4") (pintype "passive"))
      (node (ref "Q6") (pin "2") (pinfunction "S_2") (pintype "bidirectional"))
      (node (ref "R44") (pin "2") (pinfunction "2_2") (pintype "passive"))
      (node (ref "R45") (pin "1") (pinfunction "1_1") (pintype "passive"))
      (node (ref "R49") (pin "2") (pinfunction "2_2") (pintype "passive"))
    )
    (net (code "34") (name "/P7") (class "Default")
      (node (ref "C12") (pin "2") (pinfunction "2_2") (pintype "passive"))
      (node (ref "JP1") (pin "7") (pinfunction "7_7") (pintype "passive"))
      (node (ref "JP14") (pin "11") (pinfunction "11_11") (pintype "passive"))
      (node (ref "JP14") (pin "2") (pinfunction "2_2") (pintype "passive"))
      (node (ref "JP14") (pin "3") (pinfunction "3_3") (pintype "passive"))
      (node (ref "JP14") (pin "5") (pinfunction "5_5") (pintype "passive"))
      (node (ref "JP14") (pin "7") (pinfunction "7_7") (pintype "passive"))
      (node (ref "JP14") (pin "9") (pinfunction "9_9") (pintype "passive"))
      (node (ref "Q7") (pin "2") (pinfunction "S_2") (pintype "bidirectional"))
      (node (ref "R50") (pin "2") (pinfunction "2_2") (pintype "passive"))
      (node (ref "R51") (pin "1") (pinfunction "1_1") (pintype "passive"))
      (node (ref "R65") (pin "2") (pinfunction "2_2") (pintype "passive"))
    )
    (net (code "35") (name "/P8") (class "Default")
      (node (ref "C13") (pin "2") (pinfunction "2_2") (pintype "passive"))
      (node (ref "JP1") (pin "8") (pinfunction "8_8") (pintype "passive"))
      (node (ref "JP13") (pin "10") (pinfunction "10_10") (pintype "passive"))
      (node (ref "Q8") (pin "2") (pinfunction "S_2") (pintype "bidirectional"))
      (node (ref "R66") (pin "2") (pinfunction "2_2") (pintype "passive"))
      (node (ref "R67") (pin "1") (pinfunction "1_1") (pintype "passive"))
      (node (ref "R71") (pin "2") (pinfunction "2_2") (pintype "passive"))
    )
    (net (code "36") (name "/P9") (class "Default")
      (node (ref "C14") (pin "2") (pinfunction "2_2") (pintype "passive"))
      (node (ref "JP1") (pin "9") (pinfunction "9_9") (pintype "passive"))
      (node (ref "JP13") (pin "8") (pinfunction "8_8") (pintype "passive"))
      (node (ref "Q9") (pin "2") (pinfunction "S_2") (pintype "bidirectional"))
      (node (ref "R72") (pin "2") (pinfunction "2_2") (pintype "passive"))
      (node (ref "R73") (pin "1") (pinfunction "1_1") (pintype "passive"))
      (node (ref "R77") (pin "2") (pinfunction "2_2") (pintype "passive"))
    )
    (net (code "37") (name "/P10") (class "Default")
      (node (ref "C15") (pin "2") (pinfunction "2_2") (pintype "passive"))
      (node (ref "JP1") (pin "10") (pinfunction "10_10") (pintype "passive"))
      (node (ref "JP13") (pin "6") (pinfunction "6_6") (pintype "passive"))
      (node (ref "Q10") (pin "2") (pinfunction "S_2") (pintype "bidirectional"))
      (node (ref "R78") (pin "2") (pinfunction "2_2") (pintype "passive"))
      (node (ref "R79") (pin "1") (pinfunction "1_1") (pintype "passive"))
      (node (ref "R83") (pin "2") (pinfunction "2_2") (pintype "passive"))
    )
    (net (code "38") (name "/P11") (class "Default")
      (node (ref "C17") (pin "2") (pinfunction "2_2") (pintype "passive"))
      (node (ref "JP1") (pin "11") (pinfunction "11_11") (pintype "passive"))
      (node (ref "JP13") (pin "4") (pinfunction "4_4") (pintype "passive"))
      (node (ref "Q11") (pin "2") (pinfunction "S_2") (pintype "bidirectional"))
      (node (ref "R84") (pin "2") (pinfunction "2_2") (pintype "passive"))
      (node (ref "R85") (pin "1") (pinfunction "1_1") (pintype "passive"))
      (node (ref "R89") (pin "2") (pinfunction "2_2") (pintype "passive"))
    )
    (net (code "39") (name "/P12") (class "Default")
      (node (ref "C20") (pin "2") (pinfunction "2_2") (pintype "passive"))
      (node (ref "JP1") (pin "12") (pinfunction "12_12") (pintype "passive"))
      (node (ref "JP13") (pin "2") (pinfunction "2_2") (pintype "passive"))
      (node (ref "Q12") (pin "2") (pinfunction "S_2") (pintype "bidirectional"))
      (node (ref "R90") (pin "2") (pinfunction "2_2") (pintype "passive"))
      (node (ref "R91") (pin "1") (pinfunction "1_1") (pintype "passive"))
      (node (ref "R95") (pin "2") (pinfunction "2_2") (pintype "passive"))
    )
    (net (code "40") (name "/P13") (class "Default")
      (node (ref "D2") (pin "1") (pinfunction "K_1") (pintype "bidirectional"))
      (node (ref "JP1") (pin "13") (pinfunction "13_13") (pintype "passive"))
      (node (ref "JP13") (pin "1") (pinfunction "1_1") (pintype "passive"))
      (node (ref "JP13") (pin "3") (pinfunction "3_3") (pintype "passive"))
      (node (ref "JP13") (pin "5") (pinfunction "5_5") (pintype "passive"))
      (node (ref "JP13") (pin "7") (pinfunction "7_7") (pintype "passive"))
      (node (ref "JP13") (pin "9") (pinfunction "9_9") (pintype "passive"))
      (node (ref "JP14") (pin "1") (pinfunction "1_1") (pintype "passive"))
      (node (ref "Q13") (pin "2") (pinfunction "S_2") (pintype "bidirectional"))
      (node (ref "R15") (pin "2") (pinfunction "2_2") (pintype "passive"))
      (node (ref "R4") (pin "2") (pinfunction "2_2") (pintype "passive"))
      (node (ref "R59") (pin "2") (pinfunction "2_2") (pintype "passive"))
      (node (ref "R96") (pin "2") (pinfunction "2_2") (pintype "passive"))
      (node (ref "U$1") (pin "IN+") (pinfunction "IN+_IN+") (pintype "bidirectional"))
    )
    (net (code "41") (name "/S1") (class "Default")
      (node (ref "JP6") (pin "48") (pinfunction "48_48") (pintype "passive"))
      (node (ref "R10") (pin "1") (pinfunction "1_1") (pintype "passive"))
    )
    (net (code "42") (name "/S2") (class "Default")
      (node (ref "JP5") (pin "45") (pinfunction "45_45") (pintype "passive"))
      (node (ref "R30") (pin "1") (pinfunction "1_1") (pintype "passive"))
    )
    (net (code "43") (name "/S3") (class "Default")
      (node (ref "JP5") (pin "41") (pinfunction "41_41") (pintype "passive"))
      (node (ref "R24") (pin "1") (pinfunction "1_1") (pintype "passive"))
    )
    (net (code "44") (name "/S4") (class "Default")
      (node (ref "JP5") (pin "37") (pinfunction "37_37") (pintype "passive"))
      (node (ref "R36") (pin "1") (pinfunction "1_1") (pintype "passive"))
    )
    (net (code "45") (name "/S5") (class "Default")
      (node (ref "JP5") (pin "33") (pinfunction "33_33") (pintype "passive"))
      (node (ref "R42") (pin "1") (pinfunction "1_1") (pintype "passive"))
    )
    (net (code "46") (name "/S6") (class "Default")
      (node (ref "JP5") (pin "29") (pinfunction "29_29") (pintype "passive"))
      (node (ref "R48") (pin "1") (pinfunction "1_1") (pintype "passive"))
    )
    (net (code "47") (name "/S7") (class "Default")
      (node (ref "JP5") (pin "25") (pinfunction "25_25") (pintype "passive"))
      (node (ref "R64") (pin "1") (pinfunction "1_1") (pintype "passive"))
    )
    (net (code "48") (name "/S8") (class "Default")
      (node (ref "JP5") (pin "21") (pinfunction "21_21") (pintype "passive"))
      (node (ref "R70") (pin "1") (pinfunction "1_1") (pintype "passive"))
    )
    (net (code "49") (name "/S9") (class "Default")
      (node (ref "JP5") (pin "17") (pinfunction "17_17") (pintype "passive"))
      (node (ref "R76") (pin "1") (pinfunction "1_1") (pintype "passive"))
    )
    (net (code "50") (name "/S10") (class "Default")
      (node (ref "JP5") (pin "13") (pinfunction "13_13") (pintype "passive"))
      (node (ref "R82") (pin "1") (pinfunction "1_1") (pintype "passive"))
    )
    (net (code "51") (name "/S11") (class "Default")
      (node (ref "JP5") (pin "9") (pinfunction "9_9") (pintype "passive"))
      (node (ref "R88") (pin "1") (pinfunction "1_1") (pintype "passive"))
    )
    (net (code "52") (name "/S12") (class "Default")
      (node (ref "JP5") (pin "5") (pinfunction "5_5") (pintype "passive"))
      (node (ref "R94") (pin "1") (pinfunction "1_1") (pintype "passive"))
    )
    (net (code "53") (name "/SCK") (class "Default")
      (node (ref "JP6") (pin "14") (pinfunction "14_14") (pintype "passive"))
      (node (ref "U$2") (pin "JP1.4") (pinfunction "D5_JP1.4") (pintype "bidirectional"))
    )
    (net (code "54") (name "/SWTEN") (class "Default")
      (node (ref "JP6") (pin "26") (pinfunction "26_26") (pintype "passive"))
    )
    (net (code "55") (name "/V+") (class "Default")
      (node (ref "C21") (pin "1") (pinfunction "1_1") (pintype "passive"))
      (node (ref "JP5") (pin "1") (pinfunction "1_1") (pintype "passive"))
      (node (ref "R4") (pin "1") (pinfunction "1_1") (pintype "passive"))
    )
    (net (code "56") (name "/VREF1") (class "Default")
      (node (ref "C1") (pin "+") (pinfunction "+_+") (pintype "passive"))
      (node (ref "C18") (pin "1") (pinfunction "1_1") (pintype "passive"))
      (node (ref "JP2") (pin "3") (pinfunction "3_3") (pintype "passive"))
      (node (ref "JP6") (pin "28") (pinfunction "28_28") (pintype "passive"))
    )
    (net (code "57") (name "/VREF2") (class "Default")
      (node (ref "C19") (pin "1") (pinfunction "1_1") (pintype "passive"))
      (node (ref "C2") (pin "+") (pinfunction "+_+") (pintype "passive"))
      (node (ref "JP2") (pin "1") (pinfunction "1_1") (pintype "passive"))
      (node (ref "JP6") (pin "30") (pinfunction "30_30") (pintype "passive"))
    )
    (net (code "58") (name "/VREG") (class "Default")
      (node (ref "C16") (pin "1") (pinfunction "1_1") (pintype "passive"))
      (node (ref "C3") (pin "+") (pinfunction "+_+") (pintype "passive"))
      (node (ref "JP4") (pin "2") (pinfunction "2_2") (pintype "passive"))
      (node (ref "JP6") (pin "24") (pinfunction "24_24") (pintype "passive"))
    )
    (net (code "59") (name "/VTEMP1") (class "Default")
      (node (ref "JP2") (pin "2") (pinfunction "2_2") (pintype "passive"))
      (node (ref "R57") (pin "2") (pinfunction "2_2") (pintype "passive"))
    )
    (net (code "60") (name "/VTEMP2") (class "Default")
      (node (ref "JP2") (pin "4") (pinfunction "4_4") (pintype "passive"))
      (node (ref "R58") (pin "2") (pinfunction "2_2") (pintype "passive"))
    )
    (net (code "61") (name "/WDT") (class "Default")
      (node (ref "JP6") (pin "20") (pinfunction "20_20") (pintype "passive"))
    )
    (net (code "62") (name "GND") (class "Default")
      (node (ref "C1") (pin "-") (pinfunction "-_-") (pintype "passive"))
      (node (ref "C16") (pin "2") (pinfunction "2_2") (pintype "passive"))
      (node (ref "C18") (pin "2") (pinfunction "2_2") (pintype "passive"))
      (node (ref "C19") (pin "2") (pinfunction "2_2") (pintype "passive"))
      (node (ref "C2") (pin "-") (pinfunction "-_-") (pintype "passive"))
      (node (ref "C21") (pin "2") (pinfunction "2_2") (pintype "passive"))
      (node (ref "C3") (pin "-") (pinfunction "-_-") (pintype "passive"))
      (node (ref "C4") (pin "2") (pinfunction "2_2") (pintype "passive"))
      (node (ref "C5") (pin "2") (pinfunction "2_2") (pintype "passive"))
      (node (ref "D3") (pin "2") (pinfunction "A_2") (pintype "bidirectional"))
      (node (ref "H1") (pin "B3,2") (pinfunction "MOUNT_B3,2") (pintype "passive"))
      (node (ref "H2") (pin "B3,2") (pinfunction "MOUNT_B3,2") (pintype "passive"))
      (node (ref "H3") (pin "B3,2") (pinfunction "MOUNT_B3,2") (pintype "passive"))
      (node (ref "H4") (pin "B3,2") (pinfunction "MOUNT_B3,2") (pintype "passive"))
      (node (ref "JP1") (pin "1") (pinfunction "1_1") (pintype "passive"))
      (node (ref "JP10") (pin "1") (pinfunction "1_1") (pintype "passive"))
      (node (ref "JP10") (pin "10") (pinfunction "10_10") (pintype "passive"))
      (node (ref "JP10") (pin "2") (pinfunction "2_2") (pintype "passive"))
      (node (ref "JP10") (pin "3") (pinfunction "3_3") (pintype "passive"))
      (node (ref "JP10") (pin "4") (pinfunction "4_4") (pintype "passive"))
      (node (ref "JP10") (pin "5") (pinfunction "5_5") (pintype "passive"))
      (node (ref "JP10") (pin "6") (pinfunction "6_6") (pintype "passive"))
      (node (ref "JP10") (pin "7") (pinfunction "7_7") (pintype "passive"))
      (node (ref "JP10") (pin "8") (pinfunction "8_8") (pintype "passive"))
      (node (ref "JP10") (pin "9") (pinfunction "9_9") (pintype "passive"))
      (node (ref "JP6") (pin "18") (pinfunction "18_18") (pintype "passive"))
      (node (ref "JP6") (pin "36") (pinfunction "36_36") (pintype "passive"))
      (node (ref "JP6") (pin "38") (pinfunction "38_38") (pintype "passive"))
      (node (ref "LED1") (pin "C") (pinfunction "C_C") (pintype "passive"))
      (node (ref "LED2") (pin "C") (pinfunction "C_C") (pintype "passive"))
      (node (ref "LED3") (pin "C") (pinfunction "C_C") (pintype "passive"))
      (node (ref "LED4") (pin "C") (pinfunction "C_C") (pintype "passive"))
      (node (ref "R11") (pin "2") (pinfunction "2_2") (pintype "passive"))
      (node (ref "R16") (pin "1") (pinfunction "1_1") (pintype "passive"))
      (node (ref "R3") (pin "2") (pinfunction "2_2") (pintype "passive"))
      (node (ref "R57") (pin "1") (pinfunction "1_1") (pintype "passive"))
      (node (ref "R58") (pin "1") (pinfunction "1_1") (pintype "passive"))
      (node (ref "R6") (pin "2") (pinfunction "2_2") (pintype "passive"))
      (node (ref "R60") (pin "1") (pinfunction "1_1") (pintype "passive"))
      (node (ref "R7") (pin "1") (pinfunction "1_1") (pintype "passive"))
      (node (ref "U$1") (pin "IN-") (pinfunction "IN-_IN-") (pintype "bidirectional"))
      (node (ref "U$1") (pin "OUT-") (pinfunction "OUT-_OUT-") (pintype "bidirectional"))
      (node (ref "U$2") (pin "JP2.7") (pinfunction "GND_JP2.7") (pintype "power_in"))
    )
    (net (code "63") (name "Net-(JP5-Pad2)") (class "Default")
      (node (ref "JP5") (pin "2") (pinfunction "2_2") (pintype "passive"))
      (node (ref "JP7") (pin "1") (pinfunction "1_1") (pintype "passive"))
    )
    (net (code "64") (name "Net-(JP5-Pad4)") (class "Default")
      (node (ref "JP5") (pin "4") (pinfunction "4_4") (pintype "passive"))
      (node (ref "JP7") (pin "2") (pinfunction "2_2") (pintype "passive"))
    )
    (net (code "65") (name "Net-(JP5-Pad6)") (class "Default")
      (node (ref "JP5") (pin "6") (pinfunction "6_6") (pintype "passive"))
      (node (ref "JP7") (pin "3") (pinfunction "3_3") (pintype "passive"))
    )
    (net (code "66") (name "Net-(JP5-Pad8)") (class "Default")
      (node (ref "JP5") (pin "8") (pinfunction "8_8") (pintype "passive"))
      (node (ref "JP7") (pin "4") (pinfunction "4_4") (pintype "passive"))
    )
    (net (code "67") (name "Net-(JP5-Pad10)") (class "Default")
      (node (ref "JP5") (pin "10") (pinfunction "10_10") (pintype "passive"))
      (node (ref "JP7") (pin "5") (pinfunction "5_5") (pintype "passive"))
    )
    (net (code "68") (name "Net-(JP5-Pad12)") (class "Default")
      (node (ref "JP5") (pin "12") (pinfunction "12_12") (pintype "passive"))
      (node (ref "JP7") (pin "6") (pinfunction "6_6") (pintype "passive"))
    )
    (net (code "69") (name "Net-(JP5-Pad14)") (class "Default")
      (node (ref "JP5") (pin "14") (pinfunction "14_14") (pintype "passive"))
      (node (ref "JP7") (pin "7") (pinfunction "7_7") (pintype "passive"))
    )
    (net (code "70") (name "Net-(JP5-Pad16)") (class "Default")
      (node (ref "JP5") (pin "16") (pinfunction "16_16") (pintype "passive"))
      (node (ref "JP7") (pin "8") (pinfunction "8_8") (pintype "passive"))
    )
    (net (code "71") (name "Net-(JP5-Pad18)") (class "Default")
      (node (ref "JP5") (pin "18") (pinfunction "18_18") (pintype "passive"))
      (node (ref "JP7") (pin "9") (pinfunction "9_9") (pintype "passive"))
    )
    (net (code "72") (name "Net-(JP5-Pad20)") (class "Default")
      (node (ref "JP5") (pin "20") (pinfunction "20_20") (pintype "passive"))
      (node (ref "JP7") (pin "10") (pinfunction "10_10") (pintype "passive"))
    )
    (net (code "73") (name "Net-(JP5-Pad22)") (class "Default")
      (node (ref "JP5") (pin "22") (pinfunction "22_22") (pintype "passive"))
      (node (ref "JP7") (pin "11") (pinfunction "11_11") (pintype "passive"))
    )
    (net (code "74") (name "Net-(JP5-Pad24)") (class "Default")
      (node (ref "JP5") (pin "24") (pinfunction "24_24") (pintype "passive"))
      (node (ref "JP7") (pin "12") (pinfunction "12_12") (pintype "passive"))
    )
    (net (code "75") (name "Net-(JP5-Pad26)") (class "Default")
      (node (ref "JP5") (pin "26") (pinfunction "26_26") (pintype "passive"))
      (node (ref "JP7") (pin "13") (pinfunction "13_13") (pintype "passive"))
    )
    (net (code "76") (name "Net-(JP5-Pad28)") (class "Default")
      (node (ref "JP5") (pin "28") (pinfunction "28_28") (pintype "passive"))
      (node (ref "JP7") (pin "14") (pinfunction "14_14") (pintype "passive"))
    )
    (net (code "77") (name "Net-(JP5-Pad30)") (class "Default")
      (node (ref "JP5") (pin "30") (pinfunction "30_30") (pintype "passive"))
      (node (ref "JP7") (pin "15") (pinfunction "15_15") (pintype "passive"))
    )
    (net (code "78") (name "Net-(JP5-Pad32)") (class "Default")
      (node (ref "JP5") (pin "32") (pinfunction "32_32") (pintype "passive"))
      (node (ref "JP7") (pin "16") (pinfunction "16_16") (pintype "passive"))
    )
    (net (code "79") (name "Net-(JP5-Pad34)") (class "Default")
      (node (ref "JP5") (pin "34") (pinfunction "34_34") (pintype "passive"))
      (node (ref "JP7") (pin "17") (pinfunction "17_17") (pintype "passive"))
    )
    (net (code "80") (name "Net-(JP5-Pad36)") (class "Default")
      (node (ref "JP5") (pin "36") (pinfunction "36_36") (pintype "passive"))
      (node (ref "JP7") (pin "18") (pinfunction "18_18") (pintype "passive"))
    )
    (net (code "81") (name "Net-(JP5-Pad38)") (class "Default")
      (node (ref "JP5") (pin "38") (pinfunction "38_38") (pintype "passive"))
      (node (ref "JP7") (pin "19") (pinfunction "19_19") (pintype "passive"))
    )
    (net (code "82") (name "Net-(JP5-Pad40)") (class "Default")
      (node (ref "JP5") (pin "40") (pinfunction "40_40") (pintype "passive"))
      (node (ref "JP7") (pin "20") (pinfunction "20_20") (pintype "passive"))
    )
    (net (code "83") (name "Net-(JP5-Pad42)") (class "Default")
      (node (ref "JP5") (pin "42") (pinfunction "42_42") (pintype "passive"))
      (node (ref "JP7") (pin "21") (pinfunction "21_21") (pintype "passive"))
    )
    (net (code "84") (name "Net-(JP5-Pad44)") (class "Default")
      (node (ref "JP5") (pin "44") (pinfunction "44_44") (pintype "passive"))
      (node (ref "JP7") (pin "22") (pinfunction "22_22") (pintype "passive"))
    )
    (net (code "85") (name "Net-(JP5-Pad46)") (class "Default")
      (node (ref "JP5") (pin "46") (pinfunction "46_46") (pintype "passive"))
      (node (ref "JP7") (pin "23") (pinfunction "23_23") (pintype "passive"))
    )
    (net (code "86") (name "Net-(JP5-Pad48)") (class "Default")
      (node (ref "JP5") (pin "48") (pinfunction "48_48") (pintype "passive"))
      (node (ref "JP7") (pin "24") (pinfunction "24_24") (pintype "passive"))
    )
    (net (code "87") (name "Net-(JP6-Pad1)") (class "Default")
      (node (ref "JP6") (pin "1") (pinfunction "1_1") (pintype "passive"))
      (node (ref "JP8") (pin "1") (pinfunction "1_1") (pintype "passive"))
    )
    (net (code "88") (name "Net-(JP6-Pad3)") (class "Default")
      (node (ref "JP6") (pin "3") (pinfunction "3_3") (pintype "passive"))
      (node (ref "JP8") (pin "2") (pinfunction "2_2") (pintype "passive"))
    )
    (net (code "89") (name "Net-(JP6-Pad5)") (class "Default")
      (node (ref "JP6") (pin "5") (pinfunction "5_5") (pintype "passive"))
      (node (ref "JP8") (pin "3") (pinfunction "3_3") (pintype "passive"))
    )
    (net (code "90") (name "Net-(JP6-Pad7)") (class "Default")
      (node (ref "JP6") (pin "7") (pinfunction "7_7") (pintype "passive"))
      (node (ref "JP8") (pin "4") (pinfunction "4_4") (pintype "passive"))
    )
    (net (code "91") (name "Net-(JP6-Pad9)") (class "Default")
      (node (ref "JP6") (pin "9") (pinfunction "9_9") (pintype "passive"))
      (node (ref "JP8") (pin "5") (pinfunction "5_5") (pintype "passive"))
    )
    (net (code "92") (name "Net-(JP6-Pad11)") (class "Default")
      (node (ref "JP6") (pin "11") (pinfunction "11_11") (pintype "passive"))
      (node (ref "JP8") (pin "6") (pinfunction "6_6") (pintype "passive"))
    )
    (net (code "93") (name "Net-(JP6-Pad13)") (class "Default")
      (node (ref "JP6") (pin "13") (pinfunction "13_13") (pintype "passive"))
      (node (ref "JP8") (pin "7") (pinfunction "7_7") (pintype "passive"))
    )
    (net (code "94") (name "Net-(JP6-Pad15)") (class "Default")
      (node (ref "JP6") (pin "15") (pinfunction "15_15") (pintype "passive"))
      (node (ref "JP8") (pin "8") (pinfunction "8_8") (pintype "passive"))
    )
    (net (code "95") (name "Net-(JP6-Pad17)") (class "Default")
      (node (ref "JP6") (pin "17") (pinfunction "17_17") (pintype "passive"))
      (node (ref "JP8") (pin "9") (pinfunction "9_9") (pintype "passive"))
    )
    (net (code "96") (name "Net-(JP6-Pad19)") (class "Default")
      (node (ref "JP6") (pin "19") (pinfunction "19_19") (pintype "passive"))
      (node (ref "JP8") (pin "10") (pinfunction "10_10") (pintype "passive"))
    )
    (net (code "97") (name "Net-(JP6-Pad21)") (class "Default")
      (node (ref "JP6") (pin "21") (pinfunction "21_21") (pintype "passive"))
      (node (ref "JP8") (pin "11") (pinfunction "11_11") (pintype "passive"))
    )
    (net (code "98") (name "Net-(JP6-Pad23)") (class "Default")
      (node (ref "JP6") (pin "23") (pinfunction "23_23") (pintype "passive"))
      (node (ref "JP8") (pin "12") (pinfunction "12_12") (pintype "passive"))
    )
    (net (code "99") (name "Net-(JP6-Pad25)") (class "Default")
      (node (ref "JP6") (pin "25") (pinfunction "25_25") (pintype "passive"))
      (node (ref "JP8") (pin "13") (pinfunction "13_13") (pintype "passive"))
    )
    (net (code "100") (name "Net-(JP6-Pad27)") (class "Default")
      (node (ref "JP6") (pin "27") (pinfunction "27_27") (pintype "passive"))
      (node (ref "JP8") (pin "14") (pinfunction "14_14") (pintype "passive"))
    )
    (net (code "101") (name "Net-(JP6-Pad29)") (class "Default")
      (node (ref "JP6") (pin "29") (pinfunction "29_29") (pintype "passive"))
      (node (ref "JP8") (pin "15") (pinfunction "15_15") (pintype "passive"))
    )
    (net (code "102") (name "Net-(JP6-Pad31)") (class "Default")
      (node (ref "JP6") (pin "31") (pinfunction "31_31") (pintype "passive"))
      (node (ref "JP8") (pin "16") (pinfunction "16_16") (pintype "passive"))
    )
    (net (code "103") (name "Net-(JP6-Pad33)") (class "Default")
      (node (ref "JP6") (pin "33") (pinfunction "33_33") (pintype "passive"))
      (node (ref "JP8") (pin "17") (pinfunction "17_17") (pintype "passive"))
    )
    (net (code "104") (name "Net-(JP6-Pad35)") (class "Default")
      (node (ref "JP6") (pin "35") (pinfunction "35_35") (pintype "passive"))
      (node (ref "JP8") (pin "18") (pinfunction "18_18") (pintype "passive"))
    )
    (net (code "105") (name "Net-(JP6-Pad37)") (class "Default")
      (node (ref "JP6") (pin "37") (pinfunction "37_37") (pintype "passive"))
      (node (ref "JP8") (pin "19") (pinfunction "19_19") (pintype "passive"))
    )
    (net (code "106") (name "Net-(JP6-Pad39)") (class "Default")
      (node (ref "JP6") (pin "39") (pinfunction "39_39") (pintype "passive"))
      (node (ref "JP8") (pin "20") (pinfunction "20_20") (pintype "passive"))
    )
    (net (code "107") (name "Net-(JP6-Pad41)") (class "Default")
      (node (ref "JP6") (pin "41") (pinfunction "41_41") (pintype "passive"))
      (node (ref "JP8") (pin "21") (pinfunction "21_21") (pintype "passive"))
    )
    (net (code "108") (name "Net-(JP6-Pad43)") (class "Default")
      (node (ref "JP6") (pin "43") (pinfunction "43_43") (pintype "passive"))
      (node (ref "JP8") (pin "22") (pinfunction "22_22") (pintype "passive"))
    )
    (net (code "109") (name "Net-(JP6-Pad45)") (class "Default")
      (node (ref "JP6") (pin "45") (pinfunction "45_45") (pintype "passive"))
      (node (ref "JP8") (pin "23") (pinfunction "23_23") (pintype "passive"))
    )
    (net (code "110") (name "Net-(JP6-Pad47)") (class "Default")
      (node (ref "JP6") (pin "47") (pinfunction "47_47") (pintype "passive"))
      (node (ref "JP8") (pin "24") (pinfunction "24_24") (pintype "passive"))
    )
    (net (code "111") (name "Net-(JP9-Pad1)") (class "Default")
      (node (ref "JP9") (pin "1") (pinfunction "1_1") (pintype "passive"))
      (node (ref "R1") (pin "2") (pinfunction "2_2") (pintype "passive"))
    )
    (net (code "112") (name "Net-(LED1-PadA)") (class "Default")
      (node (ref "LED1") (pin "A") (pinfunction "A_A") (pintype "passive"))
      (node (ref "R53") (pin "1") (pinfunction "1_1") (pintype "passive"))
    )
    (net (code "113") (name "Net-(LED2-PadA)") (class "Default")
      (node (ref "LED2") (pin "A") (pinfunction "A_A") (pintype "passive"))
      (node (ref "R54") (pin "1") (pinfunction "1_1") (pintype "passive"))
    )
    (net (code "114") (name "Net-(LED3-PadA)") (class "Default")
      (node (ref "LED3") (pin "A") (pinfunction "A_A") (pintype "passive"))
      (node (ref "R55") (pin "1") (pinfunction "1_1") (pintype "passive"))
    )
    (net (code "115") (name "Net-(LED4-PadA)") (class "Default")
      (node (ref "LED4") (pin "A") (pinfunction "A_A") (pintype "passive"))
      (node (ref "R56") (pin "1") (pinfunction "1_1") (pintype "passive"))
    )
    (net (code "116") (name "Net-(LED5-PadC)") (class "Default")
      (node (ref "LED5") (pin "C") (pinfunction "C_C") (pintype "passive"))
      (node (ref "R11") (pin "1") (pinfunction "1_1") (pintype "passive"))
    )
    (net (code "117") (name "Net-(LED7-PadC)") (class "Default")
      (node (ref "LED7") (pin "C") (pinfunction "C_C") (pintype "passive"))
      (node (ref "R25") (pin "1") (pinfunction "1_1") (pintype "passive"))
    )
    (net (code "118") (name "Net-(LED8-PadC)") (class "Default")
      (node (ref "LED8") (pin "C") (pinfunction "C_C") (pintype "passive"))
      (node (ref "R31") (pin "1") (pinfunction "1_1") (pintype "passive"))
    )
    (net (code "119") (name "Net-(LED9-PadC)") (class "Default")
      (node (ref "LED9") (pin "C") (pinfunction "C_C") (pintype "passive"))
      (node (ref "R37") (pin "1") (pinfunction "1_1") (pintype "passive"))
    )
    (net (code "120") (name "Net-(LED10-PadC)") (class "Default")
      (node (ref "LED10") (pin "C") (pinfunction "C_C") (pintype "passive"))
      (node (ref "R43") (pin "1") (pinfunction "1_1") (pintype "passive"))
    )
    (net (code "121") (name "Net-(LED11-PadC)") (class "Default")
      (node (ref "LED11") (pin "C") (pinfunction "C_C") (pintype "passive"))
      (node (ref "R49") (pin "1") (pinfunction "1_1") (pintype "passive"))
    )
    (net (code "122") (name "Net-(LED12-PadC)") (class "Default")
      (node (ref "LED12") (pin "C") (pinfunction "C_C") (pintype "passive"))
      (node (ref "R65") (pin "1") (pinfunction "1_1") (pintype "passive"))
    )
    (net (code "123") (name "Net-(LED13-PadC)") (class "Default")
      (node (ref "LED13") (pin "C") (pinfunction "C_C") (pintype "passive"))
      (node (ref "R71") (pin "1") (pinfunction "1_1") (pintype "passive"))
    )
    (net (code "124") (name "Net-(LED14-PadC)") (class "Default")
      (node (ref "LED14") (pin "C") (pinfunction "C_C") (pintype "passive"))
      (node (ref "R77") (pin "1") (pinfunction "1_1") (pintype "passive"))
    )
    (net (code "125") (name "Net-(LED15-PadC)") (class "Default")
      (node (ref "LED15") (pin "C") (pinfunction "C_C") (pintype "passive"))
      (node (ref "R83") (pin "1") (pinfunction "1_1") (pintype "passive"))
    )
    (net (code "126") (name "Net-(LED16-PadC)") (class "Default")
      (node (ref "LED16") (pin "C") (pinfunction "C_C") (pintype "passive"))
      (node (ref "R89") (pin "1") (pinfunction "1_1") (pintype "passive"))
    )
    (net (code "127") (name "Net-(LED17-PadC)") (class "Default")
      (node (ref "LED17") (pin "C") (pinfunction "C_C") (pintype "passive"))
      (node (ref "R95") (pin "1") (pinfunction "1_1") (pintype "passive"))
    )
    (net (code "128") (name "Net-(Q1-D)") (class "Default")
      (node (ref "LED5") (pin "A") (pinfunction "A_A") (pintype "passive"))
      (node (ref "Q1") (pin "3") (pinfunction "D_3") (pintype "bidirectional"))
      (node (ref "R9") (pin "2") (pinfunction "2_2") (pintype "passive"))
    )
    (net (code "129") (name "Net-(Q1-G)") (class "Default")
      (node (ref "Q1") (pin "1") (pinfunction "G_1") (pintype "bidirectional"))
      (node (ref "R10") (pin "2") (pinfunction "2_2") (pintype "passive"))
    )
    (net (code "130") (name "Net-(Q2-D)") (class "Default")
      (node (ref "LED7") (pin "A") (pinfunction "A_A") (pintype "passive"))
      (node (ref "Q2") (pin "3") (pinfunction "D_3") (pintype "bidirectional"))
      (node (ref "R19") (pin "2") (pinfunction "2_2") (pintype "passive"))
    )
    (net (code "131") (name "Net-(Q2-G)") (class "Default")
      (node (ref "Q2") (pin "1") (pinfunction "G_1") (pintype "bidirectional"))
      (node (ref "R24") (pin "2") (pinfunction "2_2") (pintype "passive"))
    )
    (net (code "132") (name "Net-(Q4-D)") (class "Default")
      (node (ref "LED8") (pin "A") (pinfunction "A_A") (pintype "passive"))
      (node (ref "Q4") (pin "3") (pinfunction "D_3") (pintype "bidirectional"))
      (node (ref "R29") (pin "2") (pinfunction "2_2") (pintype "passive"))
    )
    (net (code "133") (name "Net-(Q4-G)") (class "Default")
      (node (ref "Q4") (pin "1") (pinfunction "G_1") (pintype "bidirectional"))
      (node (ref "R30") (pin "2") (pinfunction "2_2") (pintype "passive"))
    )
    (net (code "134") (name "Net-(Q5-D)") (class "Default")
      (node (ref "LED9") (pin "A") (pinfunction "A_A") (pintype "passive"))
      (node (ref "Q5") (pin "3") (pinfunction "D_3") (pintype "bidirectional"))
      (node (ref "R35") (pin "2") (pinfunction "2_2") (pintype "passive"))
    )
    (net (code "135") (name "Net-(Q5-G)") (class "Default")
      (node (ref "Q5") (pin "1") (pinfunction "G_1") (pintype "bidirectional"))
      (node (ref "R36") (pin "2") (pinfunction "2_2") (pintype "passive"))
    )
    (net (code "136") (name "Net-(Q6-D)") (class "Default")
      (node (ref "LED10") (pin "A") (pinfunction "A_A") (pintype "passive"))
      (node (ref "Q6") (pin "3") (pinfunction "D_3") (pintype "bidirectional"))
      (node (ref "R41") (pin "2") (pinfunction "2_2") (pintype "passive"))
    )
    (net (code "137") (name "Net-(Q6-G)") (class "Default")
      (node (ref "Q6") (pin "1") (pinfunction "G_1") (pintype "bidirectional"))
      (node (ref "R42") (pin "2") (pinfunction "2_2") (pintype "passive"))
    )
    (net (code "138") (name "Net-(Q7-D)") (class "Default")
      (node (ref "LED11") (pin "A") (pinfunction "A_A") (pintype "passive"))
      (node (ref "Q7") (pin "3") (pinfunction "D_3") (pintype "bidirectional"))
      (node (ref "R47") (pin "2") (pinfunction "2_2") (pintype "passive"))
    )
    (net (code "139") (name "Net-(Q7-G)") (class "Default")
      (node (ref "Q7") (pin "1") (pinfunction "G_1") (pintype "bidirectional"))
      (node (ref "R48") (pin "2") (pinfunction "2_2") (pintype "passive"))
    )
    (net (code "140") (name "Net-(Q8-D)") (class "Default")
      (node (ref "LED12") (pin "A") (pinfunction "A_A") (pintype "passive"))
      (node (ref "Q8") (pin "3") (pinfunction "D_3") (pintype "bidirectional"))
      (node (ref "R63") (pin "2") (pinfunction "2_2") (pintype "passive"))
    )
    (net (code "141") (name "Net-(Q8-G)") (class "Default")
      (node (ref "Q8") (pin "1") (pinfunction "G_1") (pintype "bidirectional"))
      (node (ref "R64") (pin "2") (pinfunction "2_2") (pintype "passive"))
    )
    (net (code "142") (name "Net-(Q9-D)") (class "Default")
      (node (ref "LED13") (pin "A") (pinfunction "A_A") (pintype "passive"))
      (node (ref "Q9") (pin "3") (pinfunction "D_3") (pintype "bidirectional"))
      (node (ref "R69") (pin "2") (pinfunction "2_2") (pintype "passive"))
    )
    (net (code "143") (name "Net-(Q9-G)") (class "Default")
      (node (ref "Q9") (pin "1") (pinfunction "G_1") (pintype "bidirectional"))
      (node (ref "R70") (pin "2") (pinfunction "2_2") (pintype "passive"))
    )
    (net (code "144") (name "Net-(Q10-D)") (class "Default")
      (node (ref "LED14") (pin "A") (pinfunction "A_A") (pintype "passive"))
      (node (ref "Q10") (pin "3") (pinfunction "D_3") (pintype "bidirectional"))
      (node (ref "R75") (pin "2") (pinfunction "2_2") (pintype "passive"))
    )
    (net (code "145") (name "Net-(Q10-G)") (class "Default")
      (node (ref "Q10") (pin "1") (pinfunction "G_1") (pintype "bidirectional"))
      (node (ref "R76") (pin "2") (pinfunction "2_2") (pintype "passive"))
    )
    (net (code "146") (name "Net-(Q11-D)") (class "Default")
      (node (ref "LED15") (pin "A") (pinfunction "A_A") (pintype "passive"))
      (node (ref "Q11") (pin "3") (pinfunction "D_3") (pintype "bidirectional"))
      (node (ref "R81") (pin "2") (pinfunction "2_2") (pintype "passive"))
    )
    (net (code "147") (name "Net-(Q11-G)") (class "Default")
      (node (ref "Q11") (pin "1") (pinfunction "G_1") (pintype "bidirectional"))
      (node (ref "R82") (pin "2") (pinfunction "2_2") (pintype "passive"))
    )
    (net (code "148") (name "Net-(Q12-D)") (class "Default")
      (node (ref "LED16") (pin "A") (pinfunction "A_A") (pintype "passive"))
      (node (ref "Q12") (pin "3") (pinfunction "D_3") (pintype "bidirectional"))
      (node (ref "R87") (pin "2") (pinfunction "2_2") (pintype "passive"))
    )
    (net (code "149") (name "Net-(Q12-G)") (class "Default")
      (node (ref "Q12") (pin "1") (pinfunction "G_1") (pintype "bidirectional"))
      (node (ref "R88") (pin "2") (pinfunction "2_2") (pintype "passive"))
    )
    (net (code "150") (name "Net-(Q13-D)") (class "Default")
      (node (ref "LED17") (pin "A") (pinfunction "A_A") (pintype "passive"))
      (node (ref "Q13") (pin "3") (pinfunction "D_3") (pintype "bidirectional"))
      (node (ref "R93") (pin "2") (pinfunction "2_2") (pintype "passive"))
    )
    (net (code "151") (name "Net-(Q13-G)") (class "Default")
      (node (ref "Q13") (pin "1") (pinfunction "G_1") (pintype "bidirectional"))
      (node (ref "R94") (pin "2") (pinfunction "2_2") (pintype "passive"))
    )
    (net (code "152") (name "Net-(R7-Pad2)") (class "Default")
      (node (ref "R7") (pin "2") (pinfunction "2_2") (pintype "passive"))
      (node (ref "R8") (pin "1") (pinfunction "1_1") (pintype "passive"))
    )
    (net (code "153") (name "Net-(R8-Pad2)") (class "Default")
      (node (ref "R8") (pin "2") (pinfunction "2_2") (pintype "passive"))
      (node (ref "R9") (pin "1") (pinfunction "1_1") (pintype "passive"))
    )
    (net (code "154") (name "Net-(R17-Pad2)") (class "Default")
      (node (ref "R17") (pin "2") (pinfunction "2_2") (pintype "passive"))
      (node (ref "R18") (pin "1") (pinfunction "1_1") (pintype "passive"))
    )
    (net (code "155") (name "Net-(R18-Pad2)") (class "Default")
      (node (ref "R18") (pin "2") (pinfunction "2_2") (pintype "passive"))
      (node (ref "R19") (pin "1") (pinfunction "1_1") (pintype "passive"))
    )
    (net (code "156") (name "Net-(R27-Pad2)") (class "Default")
      (node (ref "R27") (pin "2") (pinfunction "2_2") (pintype "passive"))
      (node (ref "R28") (pin "1") (pinfunction "1_1") (pintype "passive"))
    )
    (net (code "157") (name "Net-(R28-Pad2)") (class "Default")
      (node (ref "R28") (pin "2") (pinfunction "2_2") (pintype "passive"))
      (node (ref "R29") (pin "1") (pinfunction "1_1") (pintype "passive"))
    )
    (net (code "158") (name "Net-(R33-Pad2)") (class "Default")
      (node (ref "R33") (pin "2") (pinfunction "2_2") (pintype "passive"))
      (node (ref "R34") (pin "1") (pinfunction "1_1") (pintype "passive"))
    )
    (net (code "159") (name "Net-(R34-Pad2)") (class "Default")
      (node (ref "R34") (pin "2") (pinfunction "2_2") (pintype "passive"))
      (node (ref "R35") (pin "1") (pinfunction "1_1") (pintype "passive"))
    )
    (net (code "160") (name "Net-(R39-Pad2)") (class "Default")
      (node (ref "R39") (pin "2") (pinfunction "2_2") (pintype "passive"))
      (node (ref "R40") (pin "1") (pinfunction "1_1") (pintype "passive"))
    )
    (net (code "161") (name "Net-(R40-Pad2)") (class "Default")
      (node (ref "R40") (pin "2") (pinfunction "2_2") (pintype "passive"))
      (node (ref "R41") (pin "1") (pinfunction "1_1") (pintype "passive"))
    )
    (net (code "162") (name "Net-(R45-Pad2)") (class "Default")
      (node (ref "R45") (pin "2") (pinfunction "2_2") (pintype "passive"))
      (node (ref "R46") (pin "1") (pinfunction "1_1") (pintype "passive"))
    )
    (net (code "163") (name "Net-(R46-Pad2)") (class "Default")
      (node (ref "R46") (pin "2") (pinfunction "2_2") (pintype "passive"))
      (node (ref "R47") (pin "1") (pinfunction "1_1") (pintype "passive"))
    )
    (net (code "164") (name "Net-(R51-Pad2)") (class "Default")
      (node (ref "R51") (pin "2") (pinfunction "2_2") (pintype "passive"))
      (node (ref "R52") (pin "1") (pinfunction "1_1") (pintype "passive"))
    )
    (net (code "165") (name "Net-(R52-Pad2)") (class "Default")
      (node (ref "R52") (pin "2") (pinfunction "2_2") (pintype "passive"))
      (node (ref "R63") (pin "1") (pinfunction "1_1") (pintype "passive"))
    )
    (net (code "166") (name "Net-(R67-Pad2)") (class "Default")
      (node (ref "R67") (pin "2") (pinfunction "2_2") (pintype "passive"))
      (node (ref "R68") (pin "1") (pinfunction "1_1") (pintype "passive"))
    )
    (net (code "167") (name "Net-(R68-Pad2)") (class "Default")
      (node (ref "R68") (pin "2") (pinfunction "2_2") (pintype "passive"))
      (node (ref "R69") (pin "1") (pinfunction "1_1") (pintype "passive"))
    )
    (net (code "168") (name "Net-(R73-Pad2)") (class "Default")
      (node (ref "R73") (pin "2") (pinfunction "2_2") (pintype "passive"))
      (node (ref "R74") (pin "1") (pinfunction "1_1") (pintype "passive"))
    )
    (net (code "169") (name "Net-(R74-Pad2)") (class "Default")
      (node (ref "R74") (pin "2") (pinfunction "2_2") (pintype "passive"))
      (node (ref "R75") (pin "1") (pinfunction "1_1") (pintype "passive"))
    )
    (net (code "170") (name "Net-(R79-Pad2)") (class "Default")
      (node (ref "R79") (pin "2") (pinfunction "2_2") (pintype "passive"))
      (node (ref "R80") (pin "1") (pinfunction "1_1") (pintype "passive"))
    )
    (net (code "171") (name "Net-(R80-Pad2)") (class "Default")
      (node (ref "R80") (pin "2") (pinfunction "2_2") (pintype "passive"))
      (node (ref "R81") (pin "1") (pinfunction "1_1") (pintype "passive"))
    )
    (net (code "172") (name "Net-(R85-Pad2)") (class "Default")
      (node (ref "R85") (pin "2") (pinfunction "2_2") (pintype "passive"))
      (node (ref "R86") (pin "1") (pinfunction "1_1") (pintype "passive"))
    )
    (net (code "173") (name "Net-(R86-Pad2)") (class "Default")
      (node (ref "R86") (pin "2") (pinfunction "2_2") (pintype "passive"))
      (node (ref "R87") (pin "1") (pinfunction "1_1") (pintype "passive"))
    )
    (net (code "174") (name "Net-(R91-Pad2)") (class "Default")
      (node (ref "R91") (pin "2") (pinfunction "2_2") (pintype "passive"))
      (node (ref "R92") (pin "1") (pinfunction "1_1") (pintype "passive"))
    )
    (net (code "175") (name "Net-(R92-Pad2)") (class "Default")
      (node (ref "R92") (pin "2") (pinfunction "2_2") (pintype "passive"))
      (node (ref "R93") (pin "1") (pinfunction "1_1") (pintype "passive"))
    )
    (net (code "176") (name "Net-(U$2-D0)") (class "Default")
      (node (ref "JP3") (pin "1") (pinfunction "1_1") (pintype "passive"))
      (node (ref "U$2") (pin "JP1.3") (pinfunction "D0_JP1.3") (pintype "bidirectional"))
    )
    (net (code "177") (name "Net-(U$2-D1)") (class "Default")
      (node (ref "R53") (pin "2") (pinfunction "2_2") (pintype "passive"))
      (node (ref "U$2") (pin "JP2.3") (pinfunction "D1_JP2.3") (pintype "bidirectional"))
    )
    (net (code "178") (name "Net-(U$2-D2)") (class "Default")
      (node (ref "R54") (pin "2") (pinfunction "2_2") (pintype "passive"))
      (node (ref "U$2") (pin "JP2.4") (pinfunction "D2_JP2.4") (pintype "bidirectional"))
    )
    (net (code "179") (name "Net-(U$2-D3)") (class "Default")
      (node (ref "R55") (pin "2") (pinfunction "2_2") (pintype "passive"))
      (node (ref "U$2") (pin "JP2.5") (pinfunction "D3_JP2.5") (pintype "bidirectional"))
    )
    (net (code "180") (name "Net-(U$2-D4)") (class "Default")
      (node (ref "R56") (pin "2") (pinfunction "2_2") (pintype "passive"))
      (node (ref "U$2") (pin "JP2.6") (pinfunction "D4_JP2.6") (pintype "bidirectional"))
    )
    (net (code "181") (name "Net-(U$2-D6)") (class "Default")
      (node (ref "R61") (pin "1") (pinfunction "1_1") (pintype "passive"))
      (node (ref "U$2") (pin "JP1.5") (pinfunction "D6_JP1.5") (pintype "bidirectional"))
    )
    (net (code "182") (name "Net-(U$2-D7)") (class "Default")
      (node (ref "R62") (pin "1") (pinfunction "1_1") (pintype "passive"))
      (node (ref "U$2") (pin "JP1.6") (pinfunction "D7_JP1.6") (pintype "bidirectional"))
    )
    (net (code "183") (name "Net-(U$2-RST)") (class "Default")
      (node (ref "JP3") (pin "2") (pinfunction "2_2") (pintype "passive"))
      (node (ref "U$2") (pin "JP1.1") (pinfunction "RST_JP1.1") (pintype "bidirectional"))
    )
    (net (code "184") (name "unconnected-(U$2-RX-PadJP2.2)") (class "Default")
      (node (ref "U$2") (pin "JP2.2") (pinfunction "RX_JP2.2") (pintype "bidirectional"))
    )
    (net (code "185") (name "unconnected-(U$2-TX-PadJP2.1)") (class "Default")
      (node (ref "U$2") (pin "JP2.1") (pinfunction "TX_JP2.1") (pintype "bidirectional"))
    )
  )
)
